# edges_v20.net
KiCad netlist of a schematic drawn in EAGLE
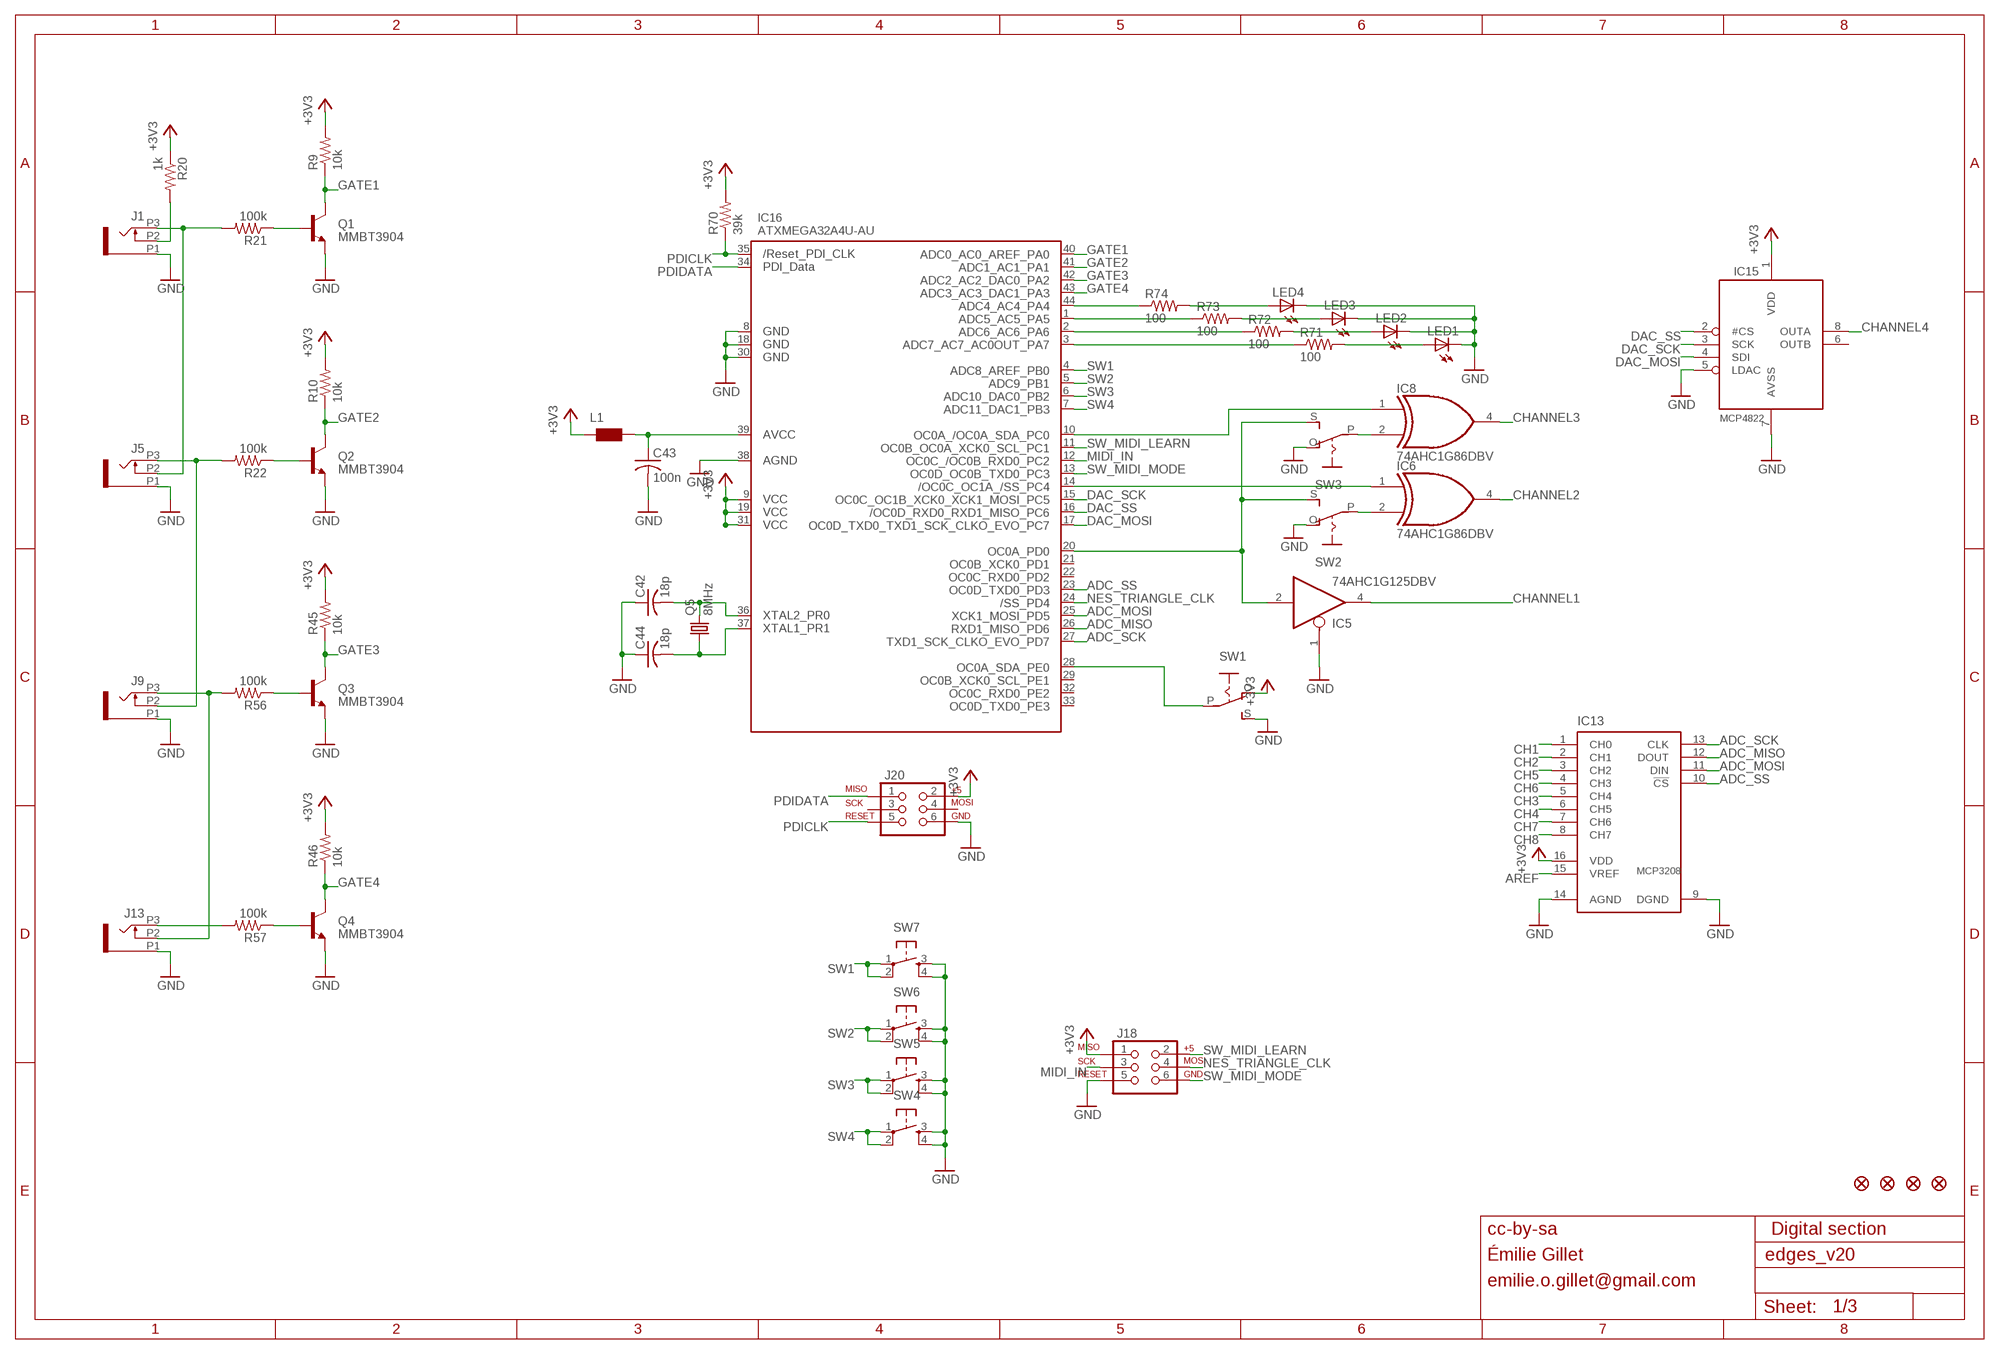
[diagram p0: schematic, sheet 1]
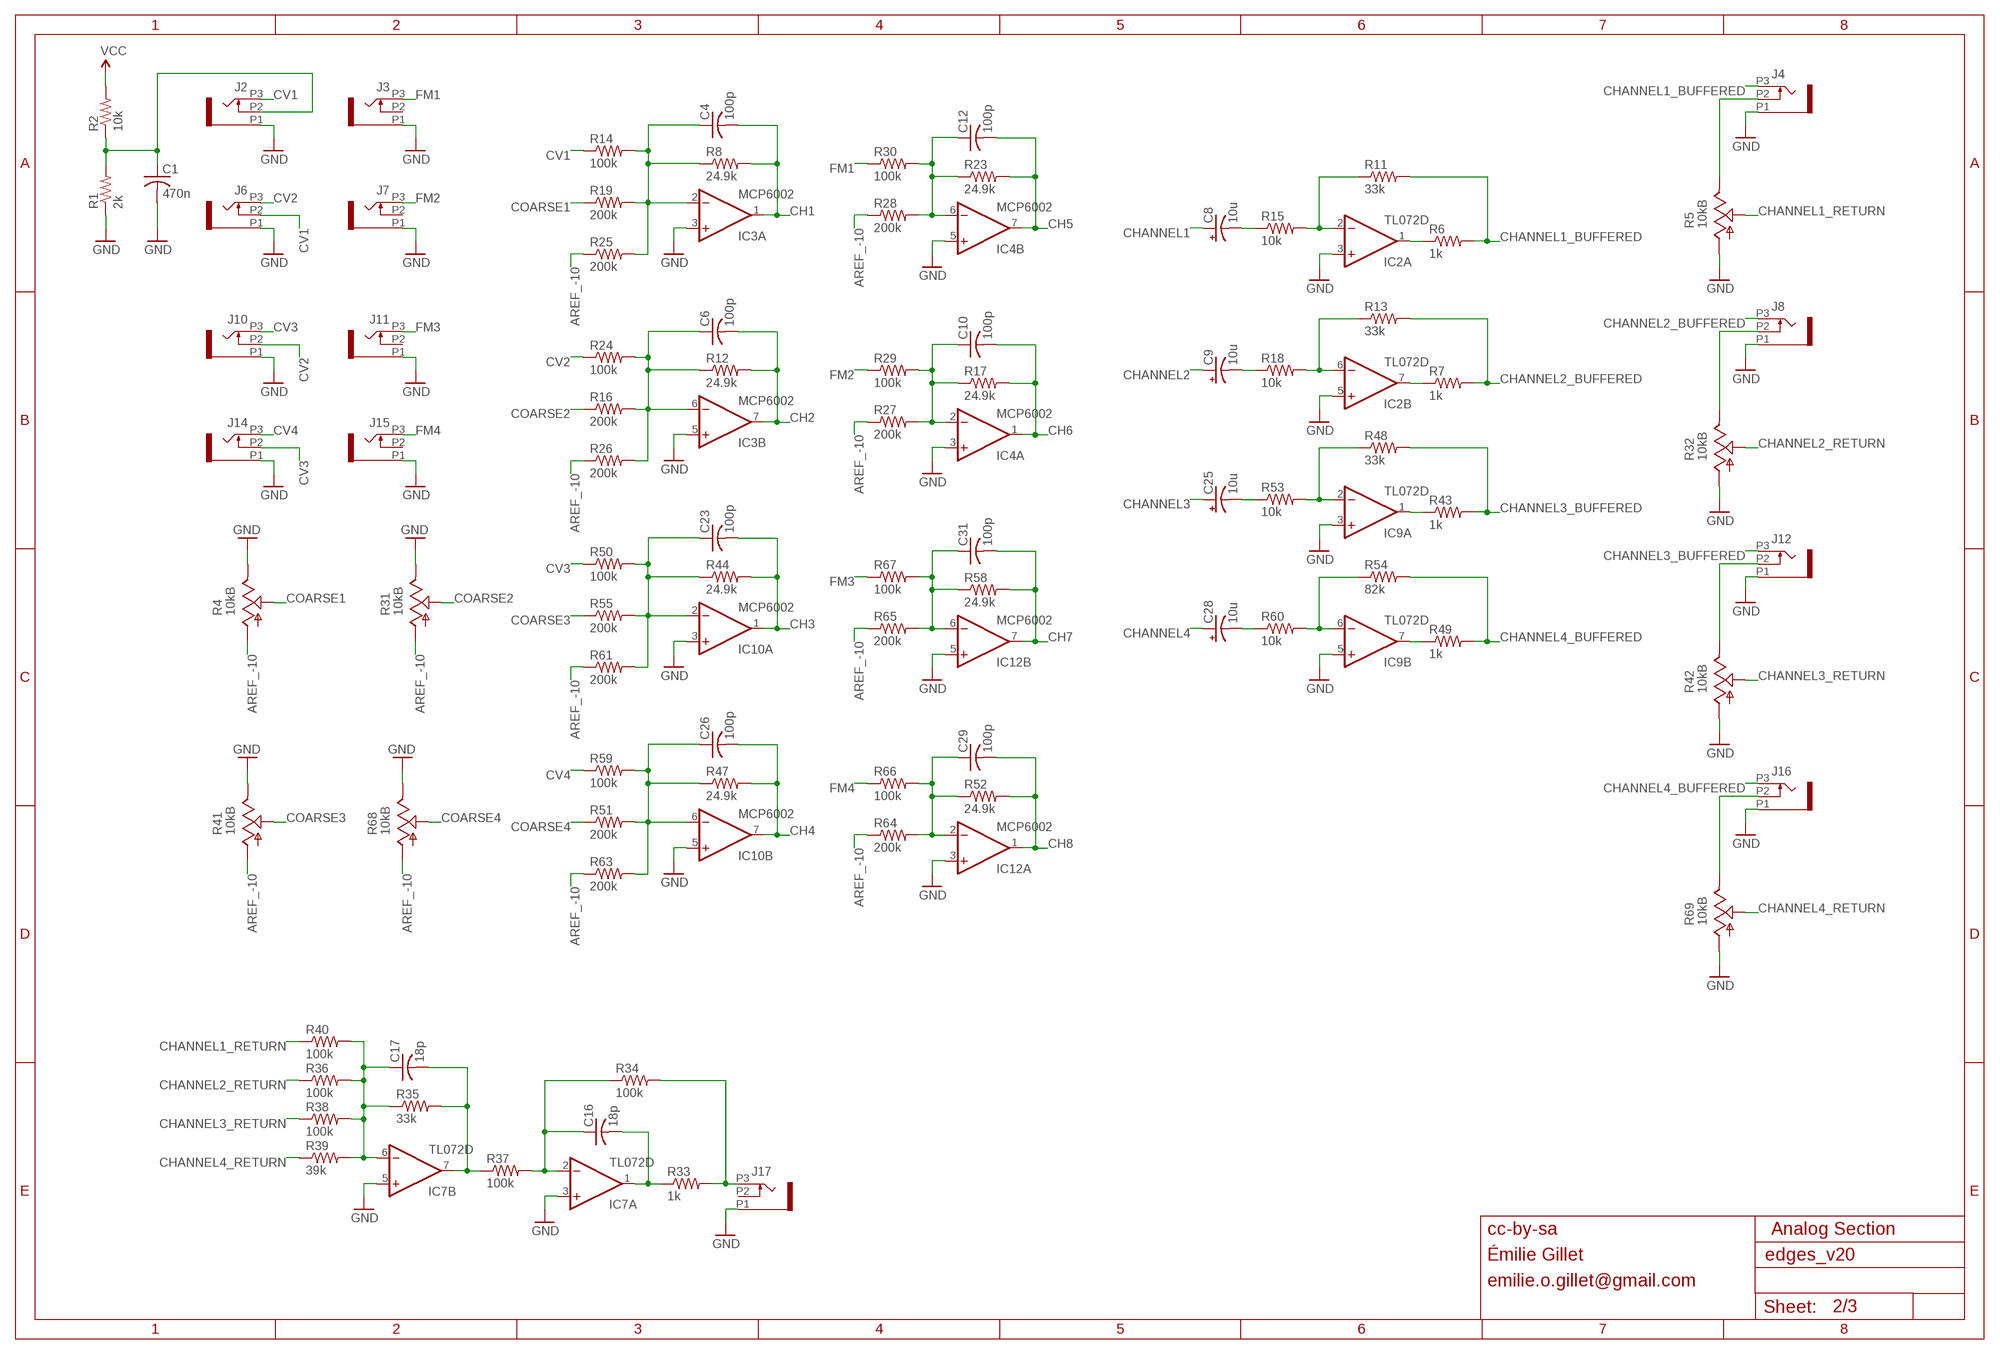
[diagram p1: schematic, sheet 2]
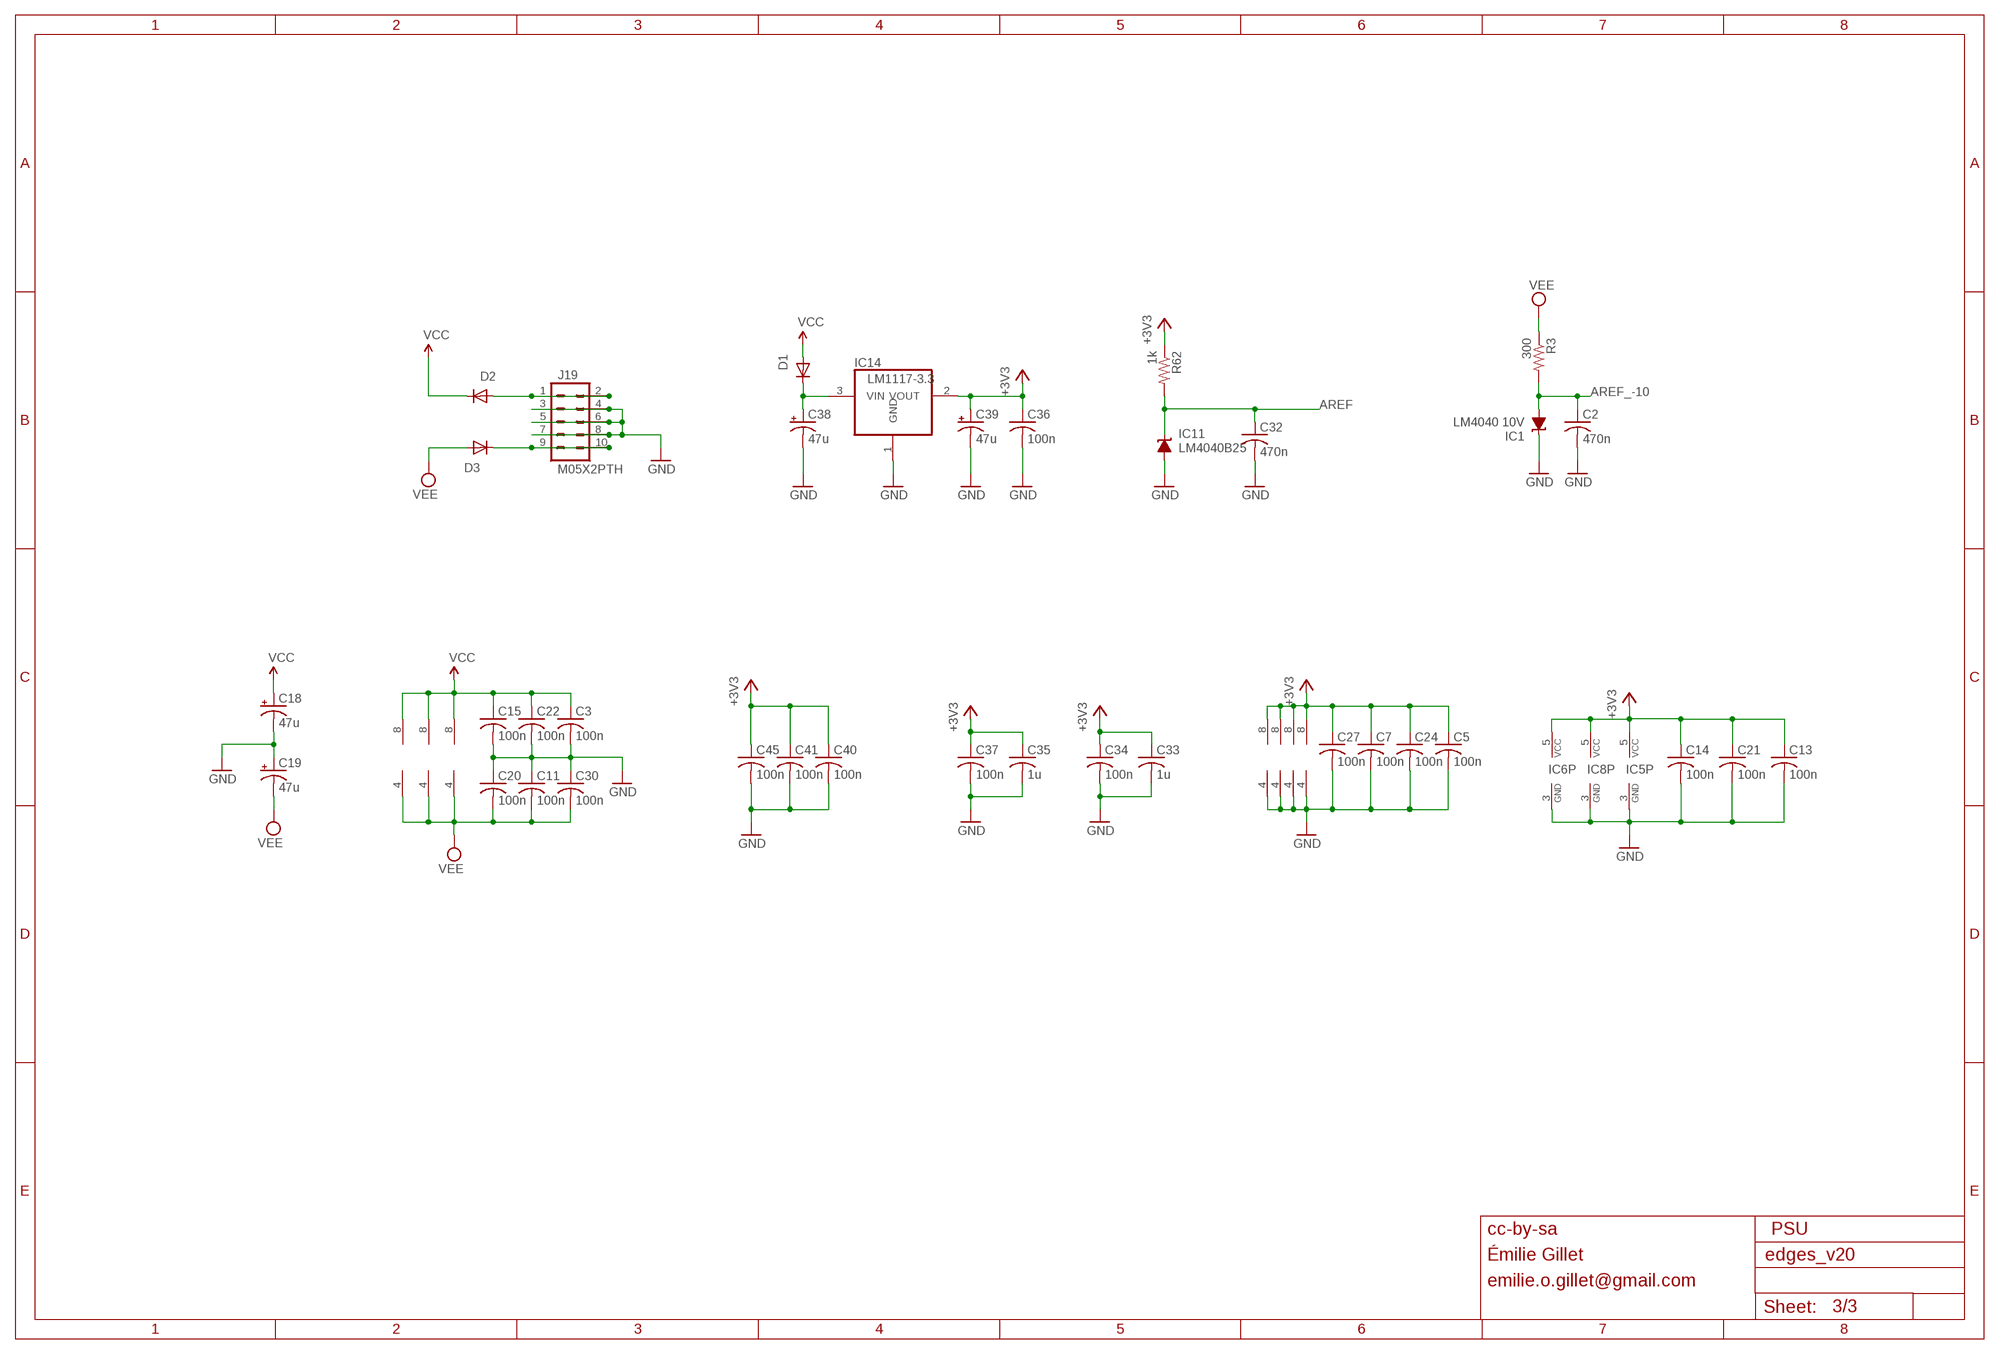
[diagram p2: schematic, sheet 3]

(export (version "E")
  (design (tool "Eeschema 10.0.6"))
  (components
    (comp (ref "C1")
      (value "470n")
      (footprint "eagle-import:C0603")
      (libsource (lib "eagle-import") (part "C-USC0603"))
    )
    (comp (ref "C4")
      (value "100p")
      (footprint "eagle-import:C0603")
      (libsource (lib "eagle-import") (part "C-USC0603"))
    )
    (comp (ref "C6")
      (value "100p")
      (footprint "eagle-import:C0603")
      (libsource (lib "eagle-import") (part "C-USC0603"))
    )
    (comp (ref "C8")
      (value "10u")
      (footprint "eagle-import:PANASONIC_B")
      (libsource (lib "eagle-import") (part "CPOL-USB"))
    )
    (comp (ref "C9")
      (value "10u")
      (footprint "eagle-import:PANASONIC_B")
      (libsource (lib "eagle-import") (part "CPOL-USB"))
    )
    (comp (ref "C10")
      (value "100p")
      (footprint "eagle-import:C0603")
      (libsource (lib "eagle-import") (part "C-USC0603"))
    )
    (comp (ref "C12")
      (value "100p")
      (footprint "eagle-import:C0603")
      (libsource (lib "eagle-import") (part "C-USC0603"))
    )
    (comp (ref "C16")
      (value "18p")
      (footprint "eagle-import:C0603")
      (libsource (lib "eagle-import") (part "C-USC0603"))
    )
    (comp (ref "C17")
      (value "18p")
      (footprint "eagle-import:C0603")
      (libsource (lib "eagle-import") (part "C-USC0603"))
    )
    (comp (ref "C23")
      (value "100p")
      (footprint "eagle-import:C0603")
      (libsource (lib "eagle-import") (part "C-USC0603"))
    )
    (comp (ref "C25")
      (value "10u")
      (footprint "eagle-import:PANASONIC_B")
      (libsource (lib "eagle-import") (part "CPOL-USB"))
    )
    (comp (ref "C26")
      (value "100p")
      (footprint "eagle-import:C0603")
      (libsource (lib "eagle-import") (part "C-USC0603"))
    )
    (comp (ref "C28")
      (value "10u")
      (footprint "eagle-import:PANASONIC_B")
      (libsource (lib "eagle-import") (part "CPOL-USB"))
    )
    (comp (ref "C29")
      (value "100p")
      (footprint "eagle-import:C0603")
      (libsource (lib "eagle-import") (part "C-USC0603"))
    )
    (comp (ref "C31")
      (value "100p")
      (footprint "eagle-import:C0603")
      (libsource (lib "eagle-import") (part "C-USC0603"))
    )
    (comp (ref "IC2")
      (value "TL072D")
      (footprint "eagle-import:SO08")
      (libsource (lib "eagle-import") (part "TL072D"))
    )
    (comp (ref "IC3")
      (value "MCP6002")
      (footprint "eagle-import:SO08")
      (libsource (lib "eagle-import") (part "TL072D"))
    )
    (comp (ref "IC4")
      (value "MCP6002")
      (footprint "eagle-import:SO08")
      (libsource (lib "eagle-import") (part "TL072D"))
    )
    (comp (ref "IC7")
      (value "TL072D")
      (footprint "eagle-import:SO08")
      (libsource (lib "eagle-import") (part "TL072D"))
    )
    (comp (ref "IC9")
      (value "TL072D")
      (footprint "eagle-import:SO08")
      (libsource (lib "eagle-import") (part "TL072D"))
    )
    (comp (ref "IC10")
      (value "MCP6002")
      (footprint "eagle-import:SO08")
      (libsource (lib "eagle-import") (part "TL072D"))
    )
    (comp (ref "IC12")
      (value "MCP6002")
      (footprint "eagle-import:SO08")
      (libsource (lib "eagle-import") (part "TL072D"))
    )
    (comp (ref "J2")
      (value "PJ301_THONKICONN6")
      (footprint "eagle-import:WQP_PJ_301M6")
      (libsource (lib "eagle-import") (part "PJ301_THONKICONN6"))
    )
    (comp (ref "J3")
      (value "PJ301_THONKICONN6")
      (footprint "eagle-import:WQP_PJ_301M6")
      (libsource (lib "eagle-import") (part "PJ301_THONKICONN6"))
    )
    (comp (ref "J4")
      (value "PJ301_THONKICONN6")
      (footprint "eagle-import:WQP_PJ_301M6")
      (libsource (lib "eagle-import") (part "PJ301_THONKICONN6"))
    )
    (comp (ref "J6")
      (value "PJ301_THONKICONN6")
      (footprint "eagle-import:WQP_PJ_301M6")
      (libsource (lib "eagle-import") (part "PJ301_THONKICONN6"))
    )
    (comp (ref "J7")
      (value "PJ301_THONKICONN6")
      (footprint "eagle-import:WQP_PJ_301M6")
      (libsource (lib "eagle-import") (part "PJ301_THONKICONN6"))
    )
    (comp (ref "J8")
      (value "PJ301_THONKICONN6")
      (footprint "eagle-import:WQP_PJ_301M6")
      (libsource (lib "eagle-import") (part "PJ301_THONKICONN6"))
    )
    (comp (ref "J10")
      (value "PJ301_THONKICONN6")
      (footprint "eagle-import:WQP_PJ_301M6")
      (libsource (lib "eagle-import") (part "PJ301_THONKICONN6"))
    )
    (comp (ref "J11")
      (value "PJ301_THONKICONN6")
      (footprint "eagle-import:WQP_PJ_301M6")
      (libsource (lib "eagle-import") (part "PJ301_THONKICONN6"))
    )
    (comp (ref "J12")
      (value "PJ301_THONKICONN6")
      (footprint "eagle-import:WQP_PJ_301M6")
      (libsource (lib "eagle-import") (part "PJ301_THONKICONN6"))
    )
    (comp (ref "J14")
      (value "PJ301_THONKICONN6")
      (footprint "eagle-import:WQP_PJ_301M6")
      (libsource (lib "eagle-import") (part "PJ301_THONKICONN6"))
    )
    (comp (ref "J15")
      (value "PJ301_THONKICONN6")
      (footprint "eagle-import:WQP_PJ_301M6")
      (libsource (lib "eagle-import") (part "PJ301_THONKICONN6"))
    )
    (comp (ref "J16")
      (value "PJ301_THONKICONN6")
      (footprint "eagle-import:WQP_PJ_301M6")
      (libsource (lib "eagle-import") (part "PJ301_THONKICONN6"))
    )
    (comp (ref "J17")
      (value "PJ301_THONKICONN6")
      (footprint "eagle-import:WQP_PJ_301M6")
      (libsource (lib "eagle-import") (part "PJ301_THONKICONN6"))
    )
    (comp (ref "R1")
      (value "2k")
      (footprint "eagle-import:R0603")
      (libsource (lib "eagle-import") (part "R-US_R0603"))
    )
    (comp (ref "R2")
      (value "10k")
      (footprint "eagle-import:R0603")
      (libsource (lib "eagle-import") (part "R-US_R0603"))
    )
    (comp (ref "R4")
      (value "10kB")
      (footprint "eagle-import:ALPS_POT_VERTICAL_PS")
      (libsource (lib "eagle-import") (part "POT_USVERTICAL_PS"))
    )
    (comp (ref "R5")
      (value "10kB")
      (footprint "eagle-import:ALPS_POT_VERTICAL_PS")
      (libsource (lib "eagle-import") (part "POT_USVERTICAL_PS"))
    )
    (comp (ref "R6")
      (value "1k")
      (footprint "eagle-import:R0603")
      (libsource (lib "eagle-import") (part "R-US_R0603"))
    )
    (comp (ref "R7")
      (value "1k")
      (footprint "eagle-import:R0603")
      (libsource (lib "eagle-import") (part "R-US_R0603"))
    )
    (comp (ref "R8")
      (value "24.9k")
      (footprint "eagle-import:R0603")
      (libsource (lib "eagle-import") (part "R-US_R0603"))
    )
    (comp (ref "R11")
      (value "33k")
      (footprint "eagle-import:R0603")
      (libsource (lib "eagle-import") (part "R-US_R0603"))
    )
    (comp (ref "R12")
      (value "24.9k")
      (footprint "eagle-import:R0603")
      (libsource (lib "eagle-import") (part "R-US_R0603"))
    )
    (comp (ref "R13")
      (value "33k")
      (footprint "eagle-import:R0603")
      (libsource (lib "eagle-import") (part "R-US_R0603"))
    )
    (comp (ref "R14")
      (value "100k")
      (footprint "eagle-import:R0603")
      (libsource (lib "eagle-import") (part "R-US_R0603"))
    )
    (comp (ref "R15")
      (value "10k")
      (footprint "eagle-import:R0603")
      (libsource (lib "eagle-import") (part "R-US_R0603"))
    )
    (comp (ref "R16")
      (value "200k")
      (footprint "eagle-import:R0603")
      (libsource (lib "eagle-import") (part "R-US_R0603"))
    )
    (comp (ref "R17")
      (value "24.9k")
      (footprint "eagle-import:R0603")
      (libsource (lib "eagle-import") (part "R-US_R0603"))
    )
    (comp (ref "R18")
      (value "10k")
      (footprint "eagle-import:R0603")
      (libsource (lib "eagle-import") (part "R-US_R0603"))
    )
    (comp (ref "R19")
      (value "200k")
      (footprint "eagle-import:R0603")
      (libsource (lib "eagle-import") (part "R-US_R0603"))
    )
    (comp (ref "R23")
      (value "24.9k")
      (footprint "eagle-import:R0603")
      (libsource (lib "eagle-import") (part "R-US_R0603"))
    )
    (comp (ref "R24")
      (value "100k")
      (footprint "eagle-import:R0603")
      (libsource (lib "eagle-import") (part "R-US_R0603"))
    )
    (comp (ref "R25")
      (value "200k")
      (footprint "eagle-import:R0603")
      (libsource (lib "eagle-import") (part "R-US_R0603"))
    )
    (comp (ref "R26")
      (value "200k")
      (footprint "eagle-import:R0603")
      (libsource (lib "eagle-import") (part "R-US_R0603"))
    )
    (comp (ref "R27")
      (value "200k")
      (footprint "eagle-import:R0603")
      (libsource (lib "eagle-import") (part "R-US_R0603"))
    )
    (comp (ref "R28")
      (value "200k")
      (footprint "eagle-import:R0603")
      (libsource (lib "eagle-import") (part "R-US_R0603"))
    )
    (comp (ref "R29")
      (value "100k")
      (footprint "eagle-import:R0603")
      (libsource (lib "eagle-import") (part "R-US_R0603"))
    )
    (comp (ref "R30")
      (value "100k")
      (footprint "eagle-import:R0603")
      (libsource (lib "eagle-import") (part "R-US_R0603"))
    )
    (comp (ref "R31")
      (value "10kB")
      (footprint "eagle-import:ALPS_POT_VERTICAL_PS")
      (libsource (lib "eagle-import") (part "POT_USVERTICAL_PS"))
    )
    (comp (ref "R32")
      (value "10kB")
      (footprint "eagle-import:ALPS_POT_VERTICAL_PS")
      (libsource (lib "eagle-import") (part "POT_USVERTICAL_PS"))
    )
    (comp (ref "R33")
      (value "1k")
      (footprint "eagle-import:R0603")
      (libsource (lib "eagle-import") (part "R-US_R0603"))
    )
    (comp (ref "R34")
      (value "100k")
      (footprint "eagle-import:R0603")
      (libsource (lib "eagle-import") (part "R-US_R0603"))
    )
    (comp (ref "R35")
      (value "33k")
      (footprint "eagle-import:R0603")
      (libsource (lib "eagle-import") (part "R-US_R0603"))
    )
    (comp (ref "R36")
      (value "100k")
      (footprint "eagle-import:R0603")
      (libsource (lib "eagle-import") (part "R-US_R0603"))
    )
    (comp (ref "R37")
      (value "100k")
      (footprint "eagle-import:R0603")
      (libsource (lib "eagle-import") (part "R-US_R0603"))
    )
    (comp (ref "R38")
      (value "100k")
      (footprint "eagle-import:R0603")
      (libsource (lib "eagle-import") (part "R-US_R0603"))
    )
    (comp (ref "R39")
      (value "39k")
      (footprint "eagle-import:R0603")
      (libsource (lib "eagle-import") (part "R-US_R0603"))
    )
    (comp (ref "R40")
      (value "100k")
      (footprint "eagle-import:R0603")
      (libsource (lib "eagle-import") (part "R-US_R0603"))
    )
    (comp (ref "R41")
      (value "10kB")
      (footprint "eagle-import:ALPS_POT_VERTICAL_PS")
      (libsource (lib "eagle-import") (part "POT_USVERTICAL_PS"))
    )
    (comp (ref "R42")
      (value "10kB")
      (footprint "eagle-import:ALPS_POT_VERTICAL_PS")
      (libsource (lib "eagle-import") (part "POT_USVERTICAL_PS"))
    )
    (comp (ref "R43")
      (value "1k")
      (footprint "eagle-import:R0603")
      (libsource (lib "eagle-import") (part "R-US_R0603"))
    )
    (comp (ref "R44")
      (value "24.9k")
      (footprint "eagle-import:R0603")
      (libsource (lib "eagle-import") (part "R-US_R0603"))
    )
    (comp (ref "R47")
      (value "24.9k")
      (footprint "eagle-import:R0603")
      (libsource (lib "eagle-import") (part "R-US_R0603"))
    )
    (comp (ref "R48")
      (value "33k")
      (footprint "eagle-import:R0603")
      (libsource (lib "eagle-import") (part "R-US_R0603"))
    )
    (comp (ref "R49")
      (value "1k")
      (footprint "eagle-import:R0603")
      (libsource (lib "eagle-import") (part "R-US_R0603"))
    )
    (comp (ref "R50")
      (value "100k")
      (footprint "eagle-import:R0603")
      (libsource (lib "eagle-import") (part "R-US_R0603"))
    )
    (comp (ref "R51")
      (value "200k")
      (footprint "eagle-import:R0603")
      (libsource (lib "eagle-import") (part "R-US_R0603"))
    )
    (comp (ref "R52")
      (value "24.9k")
      (footprint "eagle-import:R0603")
      (libsource (lib "eagle-import") (part "R-US_R0603"))
    )
    (comp (ref "R53")
      (value "10k")
      (footprint "eagle-import:R0603")
      (libsource (lib "eagle-import") (part "R-US_R0603"))
    )
    (comp (ref "R54")
      (value "82k")
      (footprint "eagle-import:R0603")
      (libsource (lib "eagle-import") (part "R-US_R0603"))
    )
    (comp (ref "R55")
      (value "200k")
      (footprint "eagle-import:R0603")
      (libsource (lib "eagle-import") (part "R-US_R0603"))
    )
    (comp (ref "R58")
      (value "24.9k")
      (footprint "eagle-import:R0603")
      (libsource (lib "eagle-import") (part "R-US_R0603"))
    )
    (comp (ref "R59")
      (value "100k")
      (footprint "eagle-import:R0603")
      (libsource (lib "eagle-import") (part "R-US_R0603"))
    )
    (comp (ref "R60")
      (value "10k")
      (footprint "eagle-import:R0603")
      (libsource (lib "eagle-import") (part "R-US_R0603"))
    )
    (comp (ref "R61")
      (value "200k")
      (footprint "eagle-import:R0603")
      (libsource (lib "eagle-import") (part "R-US_R0603"))
    )
    (comp (ref "R63")
      (value "200k")
      (footprint "eagle-import:R0603")
      (libsource (lib "eagle-import") (part "R-US_R0603"))
    )
    (comp (ref "R64")
      (value "200k")
      (footprint "eagle-import:R0603")
      (libsource (lib "eagle-import") (part "R-US_R0603"))
    )
    (comp (ref "R65")
      (value "200k")
      (footprint "eagle-import:R0603")
      (libsource (lib "eagle-import") (part "R-US_R0603"))
    )
    (comp (ref "R66")
      (value "100k")
      (footprint "eagle-import:R0603")
      (libsource (lib "eagle-import") (part "R-US_R0603"))
    )
    (comp (ref "R67")
      (value "100k")
      (footprint "eagle-import:R0603")
      (libsource (lib "eagle-import") (part "R-US_R0603"))
    )
    (comp (ref "R68")
      (value "10kB")
      (footprint "eagle-import:ALPS_POT_VERTICAL_PS")
      (libsource (lib "eagle-import") (part "POT_USVERTICAL_PS"))
    )
    (comp (ref "R69")
      (value "10kB")
      (footprint "eagle-import:ALPS_POT_VERTICAL_PS")
      (libsource (lib "eagle-import") (part "POT_USVERTICAL_PS"))
    )
    (comp (ref "C42")
      (value "18p")
      (footprint "eagle-import:C0603")
      (libsource (lib "eagle-import") (part "C-USC0603"))
    )
    (comp (ref "C43")
      (value "100n")
      (footprint "eagle-import:C0603")
      (libsource (lib "eagle-import") (part "C-USC0603"))
    )
    (comp (ref "C44")
      (value "18p")
      (footprint "eagle-import:C0603")
      (libsource (lib "eagle-import") (part "C-USC0603"))
    )
    (comp (ref "IC5")
      (value "74AHC1G125DBV")
      (footprint "eagle-import:SOT23-5")
      (libsource (lib "eagle-import") (part "741G125DBVAHC"))
    )
    (comp (ref "IC6")
      (value "74AHC1G86DBV")
      (footprint "eagle-import:SOT23-5")
      (libsource (lib "eagle-import") (part "741G86DBVAHC"))
    )
    (comp (ref "IC8")
      (value "74AHC1G86DBV")
      (footprint "eagle-import:SOT23-5")
      (libsource (lib "eagle-import") (part "741G86DBVAHC"))
    )
    (comp (ref "IC13")
      (value "MCP3208")
      (footprint "eagle-import:SO16")
      (libsource (lib "eagle-import") (part "MCP3208"))
    )
    (comp (ref "IC15")
      (value "MCP4822")
      (footprint "eagle-import:SO08")
      (libsource (lib "eagle-import") (part "MCP4822SO08"))
    )
    (comp (ref "IC16")
      (value "ATXMEGA32A4U-AU")
      (footprint "eagle-import:TQFP44")
      (libsource (lib "eagle-import") (part "AVR_XMEGA_A4_44A"))
    )
    (comp (ref "J1")
      (value "PJ301_THONKICONN6")
      (footprint "eagle-import:WQP_PJ_301M6")
      (libsource (lib "eagle-import") (part "PJ301_THONKICONN6"))
    )
    (comp (ref "J5")
      (value "PJ301_THONKICONN6")
      (footprint "eagle-import:WQP_PJ_301M6")
      (libsource (lib "eagle-import") (part "PJ301_THONKICONN6"))
    )
    (comp (ref "J9")
      (value "PJ301_THONKICONN6")
      (footprint "eagle-import:WQP_PJ_301M6")
      (libsource (lib "eagle-import") (part "PJ301_THONKICONN6"))
    )
    (comp (ref "J13")
      (value "PJ301_THONKICONN6")
      (footprint "eagle-import:WQP_PJ_301M6")
      (libsource (lib "eagle-import") (part "PJ301_THONKICONN6"))
    )
    (comp (ref "J18")
      (value "AVR_SPI_PRG_6PTH")
      (footprint "eagle-import:2X3")
      (libsource (lib "eagle-import") (part "AVR_SPI_PRG_6PTH"))
    )
    (comp (ref "J20")
      (value "AVR_SPI_PRG_6PTH")
      (footprint "eagle-import:2X3")
      (libsource (lib "eagle-import") (part "AVR_SPI_PRG_6PTH"))
    )
    (comp (ref "JP1")
      (value "FIDUCIAL1X2")
      (footprint "eagle-import:FIDUCIAL-1X2")
      (libsource (lib "eagle-import") (part "FIDUCIAL1X2"))
    )
    (comp (ref "JP2")
      (value "FIDUCIAL1X2")
      (footprint "eagle-import:FIDUCIAL-1X2")
      (libsource (lib "eagle-import") (part "FIDUCIAL1X2"))
    )
    (comp (ref "JP3")
      (value "FIDUCIAL1X2")
      (footprint "eagle-import:FIDUCIAL-1X2")
      (libsource (lib "eagle-import") (part "FIDUCIAL1X2"))
    )
    (comp (ref "JP4")
      (value "FIDUCIAL1X2")
      (footprint "eagle-import:FIDUCIAL-1X2")
      (libsource (lib "eagle-import") (part "FIDUCIAL1X2"))
    )
    (comp (ref "L1")
      (value "WE-CBF_0603")
      (footprint "eagle-import:0603")
      (libsource (lib "eagle-import") (part "WE-CBF_0603"))
    )
    (comp (ref "LED1")
      (value "LED3MM")
      (footprint "eagle-import:LED3MM")
      (libsource (lib "eagle-import") (part "LED3MM"))
    )
    (comp (ref "LED2")
      (value "LED3MM")
      (footprint "eagle-import:LED3MM")
      (libsource (lib "eagle-import") (part "LED3MM"))
    )
    (comp (ref "LED3")
      (value "LED3MM")
      (footprint "eagle-import:LED3MM")
      (libsource (lib "eagle-import") (part "LED3MM"))
    )
    (comp (ref "LED4")
      (value "LED3MM")
      (footprint "eagle-import:LED3MM")
      (libsource (lib "eagle-import") (part "LED3MM"))
    )
    (comp (ref "Q1")
      (value "MMBT3904")
      (footprint "eagle-import:SOT23-BEC")
      (libsource (lib "eagle-import") (part "-NPN-SOT23-BECMMBT3904LT1"))
    )
    (comp (ref "Q2")
      (value "MMBT3904")
      (footprint "eagle-import:SOT23-BEC")
      (libsource (lib "eagle-import") (part "-NPN-SOT23-BECMMBT3904LT1"))
    )
    (comp (ref "Q3")
      (value "MMBT3904")
      (footprint "eagle-import:SOT23-BEC")
      (libsource (lib "eagle-import") (part "-NPN-SOT23-BECMMBT3904LT1"))
    )
    (comp (ref "Q4")
      (value "MMBT3904")
      (footprint "eagle-import:SOT23-BEC")
      (libsource (lib "eagle-import") (part "-NPN-SOT23-BECMMBT3904LT1"))
    )
    (comp (ref "Q5")
      (value "8MHz")
      (footprint "eagle-import:HC49U70")
      (libsource (lib "eagle-import") (part "CRYSTALHC49U70"))
    )
    (comp (ref "R9")
      (value "10k")
      (footprint "eagle-import:R0603")
      (libsource (lib "eagle-import") (part "R-US_R0603"))
    )
    (comp (ref "R10")
      (value "10k")
      (footprint "eagle-import:R0603")
      (libsource (lib "eagle-import") (part "R-US_R0603"))
    )
    (comp (ref "R20")
      (value "1k")
      (footprint "eagle-import:R0603")
      (libsource (lib "eagle-import") (part "R-US_R0603"))
    )
    (comp (ref "R21")
      (value "100k")
      (footprint "eagle-import:R0603")
      (libsource (lib "eagle-import") (part "R-US_R0603"))
    )
    (comp (ref "R22")
      (value "100k")
      (footprint "eagle-import:R0603")
      (libsource (lib "eagle-import") (part "R-US_R0603"))
    )
    (comp (ref "R45")
      (value "10k")
      (footprint "eagle-import:R0603")
      (libsource (lib "eagle-import") (part "R-US_R0603"))
    )
    (comp (ref "R46")
      (value "10k")
      (footprint "eagle-import:R0603")
      (libsource (lib "eagle-import") (part "R-US_R0603"))
    )
    (comp (ref "R56")
      (value "100k")
      (footprint "eagle-import:R0603")
      (libsource (lib "eagle-import") (part "R-US_R0603"))
    )
    (comp (ref "R57")
      (value "100k")
      (footprint "eagle-import:R0603")
      (libsource (lib "eagle-import") (part "R-US_R0603"))
    )
    (comp (ref "R70")
      (value "39k")
      (footprint "eagle-import:R0603")
      (libsource (lib "eagle-import") (part "R-US_R0603"))
    )
    (comp (ref "R71")
      (value "100")
      (footprint "eagle-import:R0603")
      (libsource (lib "eagle-import") (part "R-US_R0603"))
    )
    (comp (ref "R72")
      (value "100")
      (footprint "eagle-import:R0603")
      (libsource (lib "eagle-import") (part "R-US_R0603"))
    )
    (comp (ref "R73")
      (value "100")
      (footprint "eagle-import:R0603")
      (libsource (lib "eagle-import") (part "R-US_R0603"))
    )
    (comp (ref "R74")
      (value "100")
      (footprint "eagle-import:R0603")
      (libsource (lib "eagle-import") (part "R-US_R0603"))
    )
    (comp (ref "SW1")
      (value "S-ON-ONSMALL_SLIDE")
      (footprint "eagle-import:ES_100SP1T6B11M2QEH_SMALL")
      (libsource (lib "eagle-import") (part "S-ON-ONSMALL_SLIDE"))
    )
    (comp (ref "SW2")
      (value "S-ON-ONSMALL_SLIDE")
      (footprint "eagle-import:ES_100SP1T6B11M2QEH_SMALL")
      (libsource (lib "eagle-import") (part "S-ON-ONSMALL_SLIDE"))
    )
    (comp (ref "SW3")
      (value "S-ON-ONSMALL_SLIDE")
      (footprint "eagle-import:ES_100SP1T6B11M2QEH_SMALL")
      (libsource (lib "eagle-import") (part "S-ON-ONSMALL_SLIDE"))
    )
    (comp (ref "SW4")
      (value "TAC_SWITCHPTH")
      (footprint "eagle-import:TACTILE-PTH")
      (libsource (lib "eagle-import") (part "TAC_SWITCHPTH"))
    )
    (comp (ref "SW5")
      (value "TAC_SWITCHPTH")
      (footprint "eagle-import:TACTILE-PTH")
      (libsource (lib "eagle-import") (part "TAC_SWITCHPTH"))
    )
    (comp (ref "SW6")
      (value "TAC_SWITCHPTH")
      (footprint "eagle-import:TACTILE-PTH")
      (libsource (lib "eagle-import") (part "TAC_SWITCHPTH"))
    )
    (comp (ref "SW7")
      (value "TAC_SWITCHPTH")
      (footprint "eagle-import:TACTILE-PTH")
      (libsource (lib "eagle-import") (part "TAC_SWITCHPTH"))
    )
    (comp (ref "C2")
      (value "470n")
      (footprint "eagle-import:C0603")
      (libsource (lib "eagle-import") (part "C-USC0603"))
    )
    (comp (ref "C3")
      (value "100n")
      (footprint "eagle-import:C0603")
      (libsource (lib "eagle-import") (part "C-USC0603"))
    )
    (comp (ref "C5")
      (value "100n")
      (footprint "eagle-import:C0603")
      (libsource (lib "eagle-import") (part "C-USC0603"))
    )
    (comp (ref "C7")
      (value "100n")
      (footprint "eagle-import:C0603")
      (libsource (lib "eagle-import") (part "C-USC0603"))
    )
    (comp (ref "C11")
      (value "100n")
      (footprint "eagle-import:C0603")
      (libsource (lib "eagle-import") (part "C-USC0603"))
    )
    (comp (ref "C13")
      (value "100n")
      (footprint "eagle-import:C0603")
      (libsource (lib "eagle-import") (part "C-USC0603"))
    )
    (comp (ref "C14")
      (value "100n")
      (footprint "eagle-import:C0603")
      (libsource (lib "eagle-import") (part "C-USC0603"))
    )
    (comp (ref "C15")
      (value "100n")
      (footprint "eagle-import:C0603")
      (libsource (lib "eagle-import") (part "C-USC0603"))
    )
    (comp (ref "C18")
      (value "47u")
      (footprint "eagle-import:PANASONIC_D")
      (libsource (lib "eagle-import") (part "CPOL-USD"))
    )
    (comp (ref "C19")
      (value "47u")
      (footprint "eagle-import:PANASONIC_D")
      (libsource (lib "eagle-import") (part "CPOL-USD"))
    )
    (comp (ref "C20")
      (value "100n")
      (footprint "eagle-import:C0603")
      (libsource (lib "eagle-import") (part "C-USC0603"))
    )
    (comp (ref "C21")
      (value "100n")
      (footprint "eagle-import:C0603")
      (libsource (lib "eagle-import") (part "C-USC0603"))
    )
    (comp (ref "C22")
      (value "100n")
      (footprint "eagle-import:C0603")
      (libsource (lib "eagle-import") (part "C-USC0603"))
    )
    (comp (ref "C24")
      (value "100n")
      (footprint "eagle-import:C0603")
      (libsource (lib "eagle-import") (part "C-USC0603"))
    )
    (comp (ref "C27")
      (value "100n")
      (footprint "eagle-import:C0603")
      (libsource (lib "eagle-import") (part "C-USC0603"))
    )
    (comp (ref "C30")
      (value "100n")
      (footprint "eagle-import:C0603")
      (libsource (lib "eagle-import") (part "C-USC0603"))
    )
    (comp (ref "C32")
      (value "470n")
      (footprint "eagle-import:C0603")
      (libsource (lib "eagle-import") (part "C-USC0603"))
    )
    (comp (ref "C33")
      (value "1u")
      (footprint "eagle-import:C0603")
      (libsource (lib "eagle-import") (part "C-USC0603"))
    )
    (comp (ref "C34")
      (value "100n")
      (footprint "eagle-import:C0603")
      (libsource (lib "eagle-import") (part "C-USC0603"))
    )
    (comp (ref "C35")
      (value "1u")
      (footprint "eagle-import:C0603")
      (libsource (lib "eagle-import") (part "C-USC0603"))
    )
    (comp (ref "C36")
      (value "100n")
      (footprint "eagle-import:C0603")
      (libsource (lib "eagle-import") (part "C-USC0603"))
    )
    (comp (ref "C37")
      (value "100n")
      (footprint "eagle-import:C0603")
      (libsource (lib "eagle-import") (part "C-USC0603"))
    )
    (comp (ref "C38")
      (value "47u")
      (footprint "eagle-import:PANASONIC_D")
      (libsource (lib "eagle-import") (part "CPOL-USD"))
    )
    (comp (ref "C39")
      (value "47u")
      (footprint "eagle-import:PANASONIC_D")
      (libsource (lib "eagle-import") (part "CPOL-USD"))
    )
    (comp (ref "C40")
      (value "100n")
      (footprint "eagle-import:C0603")
      (libsource (lib "eagle-import") (part "C-USC0603"))
    )
    (comp (ref "C41")
      (value "100n")
      (footprint "eagle-import:C0603")
      (libsource (lib "eagle-import") (part "C-USC0603"))
    )
    (comp (ref "C45")
      (value "100n")
      (footprint "eagle-import:C0603")
      (libsource (lib "eagle-import") (part "C-USC0603"))
    )
    (comp (ref "D1")
      (value "1N5819HW")
      (footprint "eagle-import:SOD123")
      (libsource (lib "eagle-import") (part "DIODE-SOD123"))
    )
    (comp (ref "D2")
      (value "1N5819HW")
      (footprint "eagle-import:SOD123")
      (libsource (lib "eagle-import") (part "DIODE-SOD123"))
    )
    (comp (ref "D3")
      (value "1N5819HW")
      (footprint "eagle-import:SOD123")
      (libsource (lib "eagle-import") (part "DIODE-SOD123"))
    )
    (comp (ref "IC1")
      (value "LM4040 10V")
      (footprint "eagle-import:DBZ_R-PDSO-G3")
      (libsource (lib "eagle-import") (part "LM4041DBZC12"))
    )
    (comp (ref "IC11")
      (value "LM4040B25")
      (footprint "eagle-import:DBZ_R-PDSO-G3")
      (libsource (lib "eagle-import") (part "LM4041DBZB12"))
    )
    (comp (ref "IC14")
      (value "LM1117-3.3")
      (footprint "eagle-import:SOT223")
      (libsource (lib "eagle-import") (part "REG1117"))
    )
    (comp (ref "J19")
      (value "M05X2PTH")
      (footprint "eagle-import:AVR_ICSP")
      (libsource (lib "eagle-import") (part "M05X2PTH"))
    )
    (comp (ref "R3")
      (value "300")
      (footprint "eagle-import:R0603")
      (libsource (lib "eagle-import") (part "resistor_R-US_R0603"))
    )
    (comp (ref "R62")
      (value "1k")
      (footprint "eagle-import:R0603")
      (libsource (lib "eagle-import") (part "R-US_R0603"))
    )
  )
  (nets
    (net (code "1") (name "+3V3") (class "Default")
      (node (ref "C13") (pin "1") (pinfunction "1_1") (pintype "passive"))
      (node (ref "C14") (pin "1") (pinfunction "1_1") (pintype "passive"))
      (node (ref "C21") (pin "1") (pinfunction "1_1") (pintype "passive"))
      (node (ref "C24") (pin "1") (pinfunction "1_1") (pintype "passive"))
      (node (ref "C27") (pin "1") (pinfunction "1_1") (pintype "passive"))
      (node (ref "C33") (pin "1") (pinfunction "1_1") (pintype "passive"))
      (node (ref "C34") (pin "1") (pinfunction "1_1") (pintype "passive"))
      (node (ref "C35") (pin "1") (pinfunction "1_1") (pintype "passive"))
      (node (ref "C36") (pin "1") (pinfunction "1_1") (pintype "passive"))
      (node (ref "C37") (pin "1") (pinfunction "1_1") (pintype "passive"))
      (node (ref "C39") (pin "+") (pinfunction "+_+") (pintype "passive"))
      (node (ref "C40") (pin "1") (pinfunction "1_1") (pintype "passive"))
      (node (ref "C41") (pin "1") (pinfunction "1_1") (pintype "passive"))
      (node (ref "C45") (pin "1") (pinfunction "1_1") (pintype "passive"))
      (node (ref "C5") (pin "1") (pinfunction "1_1") (pintype "passive"))
      (node (ref "C7") (pin "1") (pinfunction "1_1") (pintype "passive"))
      (node (ref "IC10") (pin "8") (pinfunction "V+_8") (pintype "power_in"))
      (node (ref "IC12") (pin "8") (pinfunction "V+_8") (pintype "power_in"))
      (node (ref "IC13") (pin "16") (pinfunction "VDD_16") (pintype "bidirectional"))
      (node (ref "IC14") (pin "2") (pinfunction "VOUT_2") (pintype "output"))
      (node (ref "IC15") (pin "1") (pinfunction "VDD_1") (pintype "power_in"))
      (node (ref "IC16") (pin "19") (pinfunction "VCC2_19") (pintype "bidirectional"))
      (node (ref "IC16") (pin "31") (pinfunction "VCC3_31") (pintype "bidirectional"))
      (node (ref "IC16") (pin "9") (pinfunction "VCC1_9") (pintype "bidirectional"))
      (node (ref "IC3") (pin "8") (pinfunction "V+_8") (pintype "power_in"))
      (node (ref "IC4") (pin "8") (pinfunction "V+_8") (pintype "power_in"))
      (node (ref "IC5") (pin "5") (pinfunction "VCC_5") (pintype "power_in"))
      (node (ref "IC6") (pin "5") (pinfunction "VCC_5") (pintype "power_in"))
      (node (ref "IC8") (pin "5") (pinfunction "VCC_5") (pintype "power_in"))
      (node (ref "J18") (pin "1") (pinfunction "1_1") (pintype "passive"))
      (node (ref "J20") (pin "2") (pinfunction "2_2") (pintype "passive"))
      (node (ref "L1") (pin "1") (pinfunction "1_1") (pintype "passive"))
      (node (ref "R10") (pin "2") (pinfunction "2_2") (pintype "passive"))
      (node (ref "R20") (pin "1") (pinfunction "1_1") (pintype "passive"))
      (node (ref "R45") (pin "2") (pinfunction "2_2") (pintype "passive"))
      (node (ref "R46") (pin "2") (pinfunction "2_2") (pintype "passive"))
      (node (ref "R62") (pin "1") (pinfunction "1_1") (pintype "passive"))
      (node (ref "R70") (pin "2") (pinfunction "2_2") (pintype "passive"))
      (node (ref "R9") (pin "2") (pinfunction "2_2") (pintype "passive"))
      (node (ref "SW1") (pin "O") (pinfunction "O_O") (pintype "passive"))
    )
    (net (code "2") (name "ADC_MISO") (class "Default")
      (node (ref "IC13") (pin "12") (pinfunction "DOUT_12") (pintype "bidirectional"))
      (node (ref "IC16") (pin "26") (pinfunction "PD6_26") (pintype "bidirectional"))
    )
    (net (code "3") (name "ADC_MOSI") (class "Default")
      (node (ref "IC13") (pin "11") (pinfunction "DIN_11") (pintype "bidirectional"))
      (node (ref "IC16") (pin "25") (pinfunction "PD5_25") (pintype "bidirectional"))
    )
    (net (code "4") (name "ADC_SCK") (class "Default")
      (node (ref "IC13") (pin "13") (pinfunction "CLK_13") (pintype "bidirectional"))
      (node (ref "IC16") (pin "27") (pinfunction "PD7_27") (pintype "bidirectional"))
    )
    (net (code "5") (name "ADC_SS") (class "Default")
      (node (ref "IC13") (pin "10") (pinfunction "~{CS}_10") (pintype "bidirectional"))
      (node (ref "IC16") (pin "23") (pinfunction "PD3_23") (pintype "bidirectional"))
    )
    (net (code "6") (name "AREF") (class "Default")
      (node (ref "C32") (pin "1") (pinfunction "1_1") (pintype "passive"))
      (node (ref "IC11") (pin "1") (pinfunction "C_1") (pintype "passive"))
      (node (ref "IC13") (pin "15") (pinfunction "VREF_15") (pintype "bidirectional"))
      (node (ref "R62") (pin "2") (pinfunction "2_2") (pintype "passive"))
    )
    (net (code "7") (name "AREF_-10") (class "Default")
      (node (ref "C2") (pin "1") (pinfunction "1_1") (pintype "passive"))
      (node (ref "IC1") (pin "2") (pinfunction "A_2") (pintype "passive"))
      (node (ref "R25") (pin "1") (pinfunction "1_1") (pintype "passive"))
      (node (ref "R26") (pin "1") (pinfunction "1_1") (pintype "passive"))
      (node (ref "R27") (pin "1") (pinfunction "1_1") (pintype "passive"))
      (node (ref "R28") (pin "1") (pinfunction "1_1") (pintype "passive"))
      (node (ref "R3") (pin "2") (pinfunction "2_2") (pintype "passive"))
      (node (ref "R31") (pin "P$3") (pinfunction "A_P$3") (pintype "passive"))
      (node (ref "R4") (pin "P$3") (pinfunction "A_P$3") (pintype "passive"))
      (node (ref "R41") (pin "P$3") (pinfunction "A_P$3") (pintype "passive"))
      (node (ref "R61") (pin "1") (pinfunction "1_1") (pintype "passive"))
      (node (ref "R63") (pin "1") (pinfunction "1_1") (pintype "passive"))
      (node (ref "R64") (pin "1") (pinfunction "1_1") (pintype "passive"))
      (node (ref "R65") (pin "1") (pinfunction "1_1") (pintype "passive"))
      (node (ref "R68") (pin "P$3") (pinfunction "A_P$3") (pintype "passive"))
    )
    (net (code "8") (name "CH1") (class "Default")
      (node (ref "C4") (pin "2") (pinfunction "2_2") (pintype "passive"))
      (node (ref "IC13") (pin "1") (pinfunction "CH0_1") (pintype "bidirectional"))
      (node (ref "IC3") (pin "1") (pinfunction "OUT_1") (pintype "output"))
      (node (ref "R8") (pin "2") (pinfunction "2_2") (pintype "passive"))
    )
    (net (code "9") (name "CH2") (class "Default")
      (node (ref "C6") (pin "2") (pinfunction "2_2") (pintype "passive"))
      (node (ref "IC13") (pin "2") (pinfunction "CH1_2") (pintype "bidirectional"))
      (node (ref "IC3") (pin "7") (pinfunction "OUT_7") (pintype "output"))
      (node (ref "R12") (pin "2") (pinfunction "2_2") (pintype "passive"))
    )
    (net (code "10") (name "CH3") (class "Default")
      (node (ref "C23") (pin "2") (pinfunction "2_2") (pintype "passive"))
      (node (ref "IC10") (pin "1") (pinfunction "OUT_1") (pintype "output"))
      (node (ref "IC13") (pin "5") (pinfunction "CH4_5") (pintype "bidirectional"))
      (node (ref "R44") (pin "2") (pinfunction "2_2") (pintype "passive"))
    )
    (net (code "11") (name "CH4") (class "Default")
      (node (ref "C26") (pin "2") (pinfunction "2_2") (pintype "passive"))
      (node (ref "IC10") (pin "7") (pinfunction "OUT_7") (pintype "output"))
      (node (ref "IC13") (pin "6") (pinfunction "CH5_6") (pintype "bidirectional"))
      (node (ref "R47") (pin "2") (pinfunction "2_2") (pintype "passive"))
    )
    (net (code "12") (name "CH5") (class "Default")
      (node (ref "C12") (pin "2") (pinfunction "2_2") (pintype "passive"))
      (node (ref "IC13") (pin "3") (pinfunction "CH2_3") (pintype "bidirectional"))
      (node (ref "IC4") (pin "7") (pinfunction "OUT_7") (pintype "output"))
      (node (ref "R23") (pin "2") (pinfunction "2_2") (pintype "passive"))
    )
    (net (code "13") (name "CH6") (class "Default")
      (node (ref "C10") (pin "2") (pinfunction "2_2") (pintype "passive"))
      (node (ref "IC13") (pin "4") (pinfunction "CH3_4") (pintype "bidirectional"))
      (node (ref "IC4") (pin "1") (pinfunction "OUT_1") (pintype "output"))
      (node (ref "R17") (pin "2") (pinfunction "2_2") (pintype "passive"))
    )
    (net (code "14") (name "CH7") (class "Default")
      (node (ref "C31") (pin "2") (pinfunction "2_2") (pintype "passive"))
      (node (ref "IC12") (pin "7") (pinfunction "OUT_7") (pintype "output"))
      (node (ref "IC13") (pin "7") (pinfunction "CH6_7") (pintype "bidirectional"))
      (node (ref "R58") (pin "2") (pinfunction "2_2") (pintype "passive"))
    )
    (net (code "15") (name "CH8") (class "Default")
      (node (ref "C29") (pin "2") (pinfunction "2_2") (pintype "passive"))
      (node (ref "IC12") (pin "1") (pinfunction "OUT_1") (pintype "output"))
      (node (ref "IC13") (pin "8") (pinfunction "CH7_8") (pintype "bidirectional"))
      (node (ref "R52") (pin "2") (pinfunction "2_2") (pintype "passive"))
    )
    (net (code "16") (name "CHANNEL1") (class "Default")
      (node (ref "C8") (pin "+") (pinfunction "+_+") (pintype "passive"))
      (node (ref "IC5") (pin "4") (pinfunction "O_4") (pintype "tri_state"))
    )
    (net (code "17") (name "CHANNEL1_BUFFERED") (class "Default")
      (node (ref "J4") (pin "P3") (pinfunction "3_P3") (pintype "passive"))
      (node (ref "R11") (pin "2") (pinfunction "2_2") (pintype "passive"))
      (node (ref "R6") (pin "2") (pinfunction "2_2") (pintype "passive"))
    )
    (net (code "18") (name "CHANNEL1_RETURN") (class "Default")
      (node (ref "R40") (pin "1") (pinfunction "1_1") (pintype "passive"))
      (node (ref "R5") (pin "P$2") (pinfunction "S_P$2") (pintype "passive"))
    )
    (net (code "19") (name "CHANNEL2") (class "Default")
      (node (ref "C9") (pin "+") (pinfunction "+_+") (pintype "passive"))
      (node (ref "IC6") (pin "4") (pinfunction "O_4") (pintype "output"))
    )
    (net (code "20") (name "CHANNEL2_BUFFERED") (class "Default")
      (node (ref "J8") (pin "P3") (pinfunction "3_P3") (pintype "passive"))
      (node (ref "R13") (pin "2") (pinfunction "2_2") (pintype "passive"))
      (node (ref "R7") (pin "2") (pinfunction "2_2") (pintype "passive"))
    )
    (net (code "21") (name "CHANNEL2_RETURN") (class "Default")
      (node (ref "R32") (pin "P$2") (pinfunction "S_P$2") (pintype "passive"))
      (node (ref "R36") (pin "1") (pinfunction "1_1") (pintype "passive"))
    )
    (net (code "22") (name "CHANNEL3") (class "Default")
      (node (ref "C25") (pin "+") (pinfunction "+_+") (pintype "passive"))
      (node (ref "IC8") (pin "4") (pinfunction "O_4") (pintype "output"))
    )
    (net (code "23") (name "CHANNEL3_BUFFERED") (class "Default")
      (node (ref "J12") (pin "P3") (pinfunction "3_P3") (pintype "passive"))
      (node (ref "R43") (pin "2") (pinfunction "2_2") (pintype "passive"))
      (node (ref "R48") (pin "2") (pinfunction "2_2") (pintype "passive"))
    )
    (net (code "24") (name "CHANNEL3_RETURN") (class "Default")
      (node (ref "R38") (pin "1") (pinfunction "1_1") (pintype "passive"))
      (node (ref "R42") (pin "P$2") (pinfunction "S_P$2") (pintype "passive"))
    )
    (net (code "25") (name "CHANNEL4") (class "Default")
      (node (ref "C28") (pin "+") (pinfunction "+_+") (pintype "passive"))
      (node (ref "IC15") (pin "8") (pinfunction "OUTA_8") (pintype "output"))
    )
    (net (code "26") (name "CHANNEL4_BUFFERED") (class "Default")
      (node (ref "J16") (pin "P3") (pinfunction "3_P3") (pintype "passive"))
      (node (ref "R49") (pin "2") (pinfunction "2_2") (pintype "passive"))
      (node (ref "R54") (pin "2") (pinfunction "2_2") (pintype "passive"))
    )
    (net (code "27") (name "CHANNEL4_RETURN") (class "Default")
      (node (ref "R39") (pin "1") (pinfunction "1_1") (pintype "passive"))
      (node (ref "R69") (pin "P$2") (pinfunction "S_P$2") (pintype "passive"))
    )
    (net (code "28") (name "COARSE1") (class "Default")
      (node (ref "R19") (pin "1") (pinfunction "1_1") (pintype "passive"))
      (node (ref "R4") (pin "P$2") (pinfunction "S_P$2") (pintype "passive"))
    )
    (net (code "29") (name "COARSE2") (class "Default")
      (node (ref "R16") (pin "1") (pinfunction "1_1") (pintype "passive"))
      (node (ref "R31") (pin "P$2") (pinfunction "S_P$2") (pintype "passive"))
    )
    (net (code "30") (name "COARSE3") (class "Default")
      (node (ref "R41") (pin "P$2") (pinfunction "S_P$2") (pintype "passive"))
      (node (ref "R55") (pin "1") (pinfunction "1_1") (pintype "passive"))
    )
    (net (code "31") (name "COARSE4") (class "Default")
      (node (ref "R51") (pin "1") (pinfunction "1_1") (pintype "passive"))
      (node (ref "R68") (pin "P$2") (pinfunction "S_P$2") (pintype "passive"))
    )
    (net (code "32") (name "CV1") (class "Default")
      (node (ref "J2") (pin "P3") (pinfunction "3_P3") (pintype "passive"))
      (node (ref "J6") (pin "P2") (pinfunction "2_P2") (pintype "passive"))
      (node (ref "R14") (pin "1") (pinfunction "1_1") (pintype "passive"))
    )
    (net (code "33") (name "CV2") (class "Default")
      (node (ref "J10") (pin "P2") (pinfunction "2_P2") (pintype "passive"))
      (node (ref "J6") (pin "P3") (pinfunction "3_P3") (pintype "passive"))
      (node (ref "R24") (pin "1") (pinfunction "1_1") (pintype "passive"))
    )
    (net (code "34") (name "CV3") (class "Default")
      (node (ref "J10") (pin "P3") (pinfunction "3_P3") (pintype "passive"))
      (node (ref "J14") (pin "P2") (pinfunction "2_P2") (pintype "passive"))
      (node (ref "R50") (pin "1") (pinfunction "1_1") (pintype "passive"))
    )
    (net (code "35") (name "CV4") (class "Default")
      (node (ref "J14") (pin "P3") (pinfunction "3_P3") (pintype "passive"))
      (node (ref "R59") (pin "1") (pinfunction "1_1") (pintype "passive"))
    )
    (net (code "36") (name "DAC_MOSI") (class "Default")
      (node (ref "IC15") (pin "4") (pinfunction "SDI_4") (pintype "input"))
      (node (ref "IC16") (pin "17") (pinfunction "PC7_17") (pintype "bidirectional"))
    )
    (net (code "37") (name "DAC_SCK") (class "Default")
      (node (ref "IC15") (pin "3") (pinfunction "SCK_3") (pintype "input"))
      (node (ref "IC16") (pin "15") (pinfunction "PC5_15") (pintype "bidirectional"))
    )
    (net (code "38") (name "DAC_SS") (class "Default")
      (node (ref "IC15") (pin "2") (pinfunction "#CS_2") (pintype "input"))
      (node (ref "IC16") (pin "16") (pinfunction "PC6_16") (pintype "bidirectional"))
    )
    (net (code "39") (name "FM1") (class "Default")
      (node (ref "J3") (pin "P3") (pinfunction "3_P3") (pintype "passive"))
      (node (ref "R30") (pin "1") (pinfunction "1_1") (pintype "passive"))
    )
    (net (code "40") (name "FM2") (class "Default")
      (node (ref "J7") (pin "P3") (pinfunction "3_P3") (pintype "passive"))
      (node (ref "R29") (pin "1") (pinfunction "1_1") (pintype "passive"))
    )
    (net (code "41") (name "FM3") (class "Default")
      (node (ref "J11") (pin "P3") (pinfunction "3_P3") (pintype "passive"))
      (node (ref "R67") (pin "1") (pinfunction "1_1") (pintype "passive"))
    )
    (net (code "42") (name "FM4") (class "Default")
      (node (ref "J15") (pin "P3") (pinfunction "3_P3") (pintype "passive"))
      (node (ref "R66") (pin "1") (pinfunction "1_1") (pintype "passive"))
    )
    (net (code "43") (name "GATE1") (class "Default")
      (node (ref "IC16") (pin "40") (pinfunction "PA0_40") (pintype "bidirectional"))
      (node (ref "Q1") (pin "C") (pinfunction "C_C") (pintype "passive"))
      (node (ref "R9") (pin "1") (pinfunction "1_1") (pintype "passive"))
    )
    (net (code "44") (name "GATE2") (class "Default")
      (node (ref "IC16") (pin "41") (pinfunction "PA1_41") (pintype "bidirectional"))
      (node (ref "Q2") (pin "C") (pinfunction "C_C") (pintype "passive"))
      (node (ref "R10") (pin "1") (pinfunction "1_1") (pintype "passive"))
    )
    (net (code "45") (name "GATE3") (class "Default")
      (node (ref "IC16") (pin "42") (pinfunction "PA2_42") (pintype "bidirectional"))
      (node (ref "Q3") (pin "C") (pinfunction "C_C") (pintype "passive"))
      (node (ref "R45") (pin "1") (pinfunction "1_1") (pintype "passive"))
    )
    (net (code "46") (name "GATE4") (class "Default")
      (node (ref "IC16") (pin "43") (pinfunction "PA3_43") (pintype "bidirectional"))
      (node (ref "Q4") (pin "C") (pinfunction "C_C") (pintype "passive"))
      (node (ref "R46") (pin "1") (pinfunction "1_1") (pintype "passive"))
    )
    (net (code "47") (name "GND") (class "Default")
      (node (ref "C1") (pin "2") (pinfunction "2_2") (pintype "passive"))
      (node (ref "C11") (pin "1") (pinfunction "1_1") (pintype "passive"))
      (node (ref "C13") (pin "2") (pinfunction "2_2") (pintype "passive"))
      (node (ref "C14") (pin "2") (pinfunction "2_2") (pintype "passive"))
      (node (ref "C15") (pin "2") (pinfunction "2_2") (pintype "passive"))
      (node (ref "C18") (pin "-") (pinfunction "-_-") (pintype "passive"))
      (node (ref "C19") (pin "+") (pinfunction "+_+") (pintype "passive"))
      (node (ref "C2") (pin "2") (pinfunction "2_2") (pintype "passive"))
      (node (ref "C20") (pin "1") (pinfunction "1_1") (pintype "passive"))
      (node (ref "C21") (pin "2") (pinfunction "2_2") (pintype "passive"))
      (node (ref "C22") (pin "2") (pinfunction "2_2") (pintype "passive"))
      (node (ref "C24") (pin "2") (pinfunction "2_2") (pintype "passive"))
      (node (ref "C27") (pin "2") (pinfunction "2_2") (pintype "passive"))
      (node (ref "C3") (pin "2") (pinfunction "2_2") (pintype "passive"))
      (node (ref "C30") (pin "1") (pinfunction "1_1") (pintype "passive"))
      (node (ref "C32") (pin "2") (pinfunction "2_2") (pintype "passive"))
      (node (ref "C33") (pin "2") (pinfunction "2_2") (pintype "passive"))
      (node (ref "C34") (pin "2") (pinfunction "2_2") (pintype "passive"))
      (node (ref "C35") (pin "2") (pinfunction "2_2") (pintype "passive"))
      (node (ref "C36") (pin "2") (pinfunction "2_2") (pintype "passive"))
      (node (ref "C37") (pin "2") (pinfunction "2_2") (pintype "passive"))
      (node (ref "C38") (pin "-") (pinfunction "-_-") (pintype "passive"))
      (node (ref "C39") (pin "-") (pinfunction "-_-") (pintype "passive"))
      (node (ref "C40") (pin "2") (pinfunction "2_2") (pintype "passive"))
      (node (ref "C41") (pin "2") (pinfunction "2_2") (pintype "passive"))
      (node (ref "C42") (pin "1") (pinfunction "1_1") (pintype "passive"))
      (node (ref "C43") (pin "2") (pinfunction "2_2") (pintype "passive"))
      (node (ref "C44") (pin "1") (pinfunction "1_1") (pintype "passive"))
      (node (ref "C45") (pin "2") (pinfunction "2_2") (pintype "passive"))
      (node (ref "C5") (pin "2") (pinfunction "2_2") (pintype "passive"))
      (node (ref "C7") (pin "2") (pinfunction "2_2") (pintype "passive"))
      (node (ref "IC1") (pin "1") (pinfunction "C_1") (pintype "passive"))
      (node (ref "IC10") (pin "3") (pinfunction "+IN_3") (pintype "input"))
      (node (ref "IC10") (pin "4") (pinfunction "V-_4") (pintype "power_in"))
      (node (ref "IC10") (pin "5") (pinfunction "+IN_5") (pintype "input"))
      (node (ref "IC11") (pin "2") (pinfunction "A_2") (pintype "passive"))
      (node (ref "IC12") (pin "3") (pinfunction "+IN_3") (pintype "input"))
      (node (ref "IC12") (pin "4") (pinfunction "V-_4") (pintype "power_in"))
      (node (ref "IC12") (pin "5") (pinfunction "+IN_5") (pintype "input"))
      (node (ref "IC13") (pin "14") (pinfunction "AGND_14") (pintype "bidirectional"))
      (node (ref "IC13") (pin "9") (pinfunction "DGND_9") (pintype "bidirectional"))
      (node (ref "IC14") (pin "1") (pinfunction "GND_1") (pintype "power_in"))
      (node (ref "IC15") (pin "5") (pinfunction "LDAC_5") (pintype "input"))
      (node (ref "IC15") (pin "7") (pinfunction "AVSS_7") (pintype "power_in"))
      (node (ref "IC16") (pin "18") (pinfunction "GND2_18") (pintype "bidirectional"))
      (node (ref "IC16") (pin "30") (pinfunction "GND3_30") (pintype "bidirectional"))
      (node (ref "IC16") (pin "38") (pinfunction "AGND_38") (pintype "bidirectional"))
      (node (ref "IC16") (pin "8") (pinfunction "GND1_8") (pintype "bidirectional"))
      (node (ref "IC2") (pin "3") (pinfunction "+IN_3") (pintype "input"))
      (node (ref "IC2") (pin "5") (pinfunction "+IN_5") (pintype "input"))
      (node (ref "IC3") (pin "3") (pinfunction "+IN_3") (pintype "input"))
      (node (ref "IC3") (pin "4") (pinfunction "V-_4") (pintype "power_in"))
      (node (ref "IC3") (pin "5") (pinfunction "+IN_5") (pintype "input"))
      (node (ref "IC4") (pin "3") (pinfunction "+IN_3") (pintype "input"))
      (node (ref "IC4") (pin "4") (pinfunction "V-_4") (pintype "power_in"))
      (node (ref "IC4") (pin "5") (pinfunction "+IN_5") (pintype "input"))
      (node (ref "IC5") (pin "1") (pinfunction "OE_1") (pintype "input"))
      (node (ref "IC5") (pin "3") (pinfunction "GND_3") (pintype "power_in"))
      (node (ref "IC6") (pin "3") (pinfunction "GND_3") (pintype "power_in"))
      (node (ref "IC7") (pin "3") (pinfunction "+IN_3") (pintype "input"))
      (node (ref "IC7") (pin "5") (pinfunction "+IN_5") (pintype "input"))
      (node (ref "IC8") (pin "3") (pinfunction "GND_3") (pintype "power_in"))
      (node (ref "IC9") (pin "3") (pinfunction "+IN_3") (pintype "input"))
      (node (ref "IC9") (pin "5") (pinfunction "+IN_5") (pintype "input"))
      (node (ref "J1") (pin "P1") (pinfunction "1_P1") (pintype "passive"))
      (node (ref "J10") (pin "P1") (pinfunction "1_P1") (pintype "passive"))
      (node (ref "J11") (pin "P1") (pinfunction "1_P1") (pintype "passive"))
      (node (ref "J12") (pin "P1") (pinfunction "1_P1") (pintype "passive"))
      (node (ref "J13") (pin "P1") (pinfunction "1_P1") (pintype "passive"))
      (node (ref "J14") (pin "P1") (pinfunction "1_P1") (pintype "passive"))
      (node (ref "J15") (pin "P1") (pinfunction "1_P1") (pintype "passive"))
      (node (ref "J16") (pin "P1") (pinfunction "1_P1") (pintype "passive"))
      (node (ref "J17") (pin "P1") (pinfunction "1_P1") (pintype "passive"))
      (node (ref "J18") (pin "5") (pinfunction "5_5") (pintype "passive"))
      (node (ref "J19") (pin "3") (pinfunction "3_3") (pintype "passive"))
      (node (ref "J19") (pin "4") (pinfunction "4_4") (pintype "passive"))
      (node (ref "J19") (pin "5") (pinfunction "5_5") (pintype "passive"))
      (node (ref "J19") (pin "6") (pinfunction "6_6") (pintype "passive"))
      (node (ref "J19") (pin "7") (pinfunction "7_7") (pintype "passive"))
      (node (ref "J19") (pin "8") (pinfunction "8_8") (pintype "passive"))
      (node (ref "J2") (pin "P1") (pinfunction "1_P1") (pintype "passive"))
      (node (ref "J20") (pin "6") (pinfunction "6_6") (pintype "passive"))
      (node (ref "J3") (pin "P1") (pinfunction "1_P1") (pintype "passive"))
      (node (ref "J4") (pin "P1") (pinfunction "1_P1") (pintype "passive"))
      (node (ref "J5") (pin "P1") (pinfunction "1_P1") (pintype "passive"))
      (node (ref "J6") (pin "P1") (pinfunction "1_P1") (pintype "passive"))
      (node (ref "J7") (pin "P1") (pinfunction "1_P1") (pintype "passive"))
      (node (ref "J8") (pin "P1") (pinfunction "1_P1") (pintype "passive"))
      (node (ref "J9") (pin "P1") (pinfunction "1_P1") (pintype "passive"))
      (node (ref "LED1") (pin "K") (pinfunction "C_K") (pintype "passive"))
      (node (ref "LED2") (pin "K") (pinfunction "C_K") (pintype "passive"))
      (node (ref "LED3") (pin "K") (pinfunction "C_K") (pintype "passive"))
      (node (ref "LED4") (pin "K") (pinfunction "C_K") (pintype "passive"))
      (node (ref "Q1") (pin "E") (pinfunction "E_E") (pintype "passive"))
      (node (ref "Q2") (pin "E") (pinfunction "E_E") (pintype "passive"))
      (node (ref "Q3") (pin "E") (pinfunction "E_E") (pintype "passive"))
      (node (ref "Q4") (pin "E") (pinfunction "E_E") (pintype "passive"))
      (node (ref "R1") (pin "1") (pinfunction "1_1") (pintype "passive"))
      (node (ref "R31") (pin "P$1") (pinfunction "E_P$1") (pintype "passive"))
      (node (ref "R32") (pin "P$3") (pinfunction "A_P$3") (pintype "passive"))
      (node (ref "R4") (pin "P$1") (pinfunction "E_P$1") (pintype "passive"))
      (node (ref "R41") (pin "P$1") (pinfunction "E_P$1") (pintype "passive"))
      (node (ref "R42") (pin "P$3") (pinfunction "A_P$3") (pintype "passive"))
      (node (ref "R5") (pin "P$3") (pinfunction "A_P$3") (pintype "passive"))
      (node (ref "R68") (pin "P$1") (pinfunction "E_P$1") (pintype "passive"))
      (node (ref "R69") (pin "P$3") (pinfunction "A_P$3") (pintype "passive"))
      (node (ref "SW1") (pin "S") (pinfunction "S_S") (pintype "passive"))
      (node (ref "SW2") (pin "O") (pinfunction "O_O") (pintype "passive"))
      (node (ref "SW3") (pin "O") (pinfunction "O_O") (pintype "passive"))
      (node (ref "SW4") (pin "3") (pinfunction "3_3") (pintype "passive"))
      (node (ref "SW4") (pin "4") (pinfunction "4_4") (pintype "passive"))
      (node (ref "SW5") (pin "3") (pinfunction "3_3") (pintype "passive"))
      (node (ref "SW5") (pin "4") (pinfunction "4_4") (pintype "passive"))
      (node (ref "SW6") (pin "3") (pinfunction "3_3") (pintype "passive"))
      (node (ref "SW6") (pin "4") (pinfunction "4_4") (pintype "passive"))
      (node (ref "SW7") (pin "3") (pinfunction "3_3") (pintype "passive"))
      (node (ref "SW7") (pin "4") (pinfunction "4_4") (pintype "passive"))
    )
    (net (code "48") (name "MIDI_IN") (class "Default")
      (node (ref "IC16") (pin "12") (pinfunction "PC2_12") (pintype "bidirectional"))
      (node (ref "J18") (pin "3") (pinfunction "3_3") (pintype "passive"))
    )
    (net (code "49") (name "NES_TRIANGLE_CLK") (class "Default")
      (node (ref "IC16") (pin "24") (pinfunction "PD4_24") (pintype "bidirectional"))
      (node (ref "J18") (pin "4") (pinfunction "4_4") (pintype "passive"))
    )
    (net (code "50") (name "Net-(C8-Pad-)") (class "Default")
      (node (ref "C8") (pin "-") (pinfunction "-_-") (pintype "passive"))
      (node (ref "R15") (pin "1") (pinfunction "1_1") (pintype "passive"))
    )
    (net (code "51") (name "Net-(C9-Pad-)") (class "Default")
      (node (ref "C9") (pin "-") (pinfunction "-_-") (pintype "passive"))
      (node (ref "R18") (pin "1") (pinfunction "1_1") (pintype "passive"))
    )
    (net (code "52") (name "Net-(C25-Pad-)") (class "Default")
      (node (ref "C25") (pin "-") (pinfunction "-_-") (pintype "passive"))
      (node (ref "R53") (pin "1") (pinfunction "1_1") (pintype "passive"))
    )
    (net (code "53") (name "Net-(C28-Pad-)") (class "Default")
      (node (ref "C28") (pin "-") (pinfunction "-_-") (pintype "passive"))
      (node (ref "R60") (pin "1") (pinfunction "1_1") (pintype "passive"))
    )
    (net (code "54") (name "Net-(D2-PadA)") (class "Default")
      (node (ref "D2") (pin "A") (pinfunction "A_A") (pintype "passive"))
      (node (ref "J19") (pin "1") (pinfunction "1_1") (pintype "passive"))
      (node (ref "J19") (pin "2") (pinfunction "2_2") (pintype "passive"))
    )
    (net (code "55") (name "Net-(D3-PadC)") (class "Default")
      (node (ref "D3") (pin "C") (pinfunction "C_C") (pintype "passive"))
      (node (ref "J19") (pin "10") (pinfunction "10_10") (pintype "passive"))
      (node (ref "J19") (pin "9") (pinfunction "9_9") (pintype "passive"))
    )
    (net (code "56") (name "Net-(IC2A--IN)") (class "Default")
      (node (ref "IC2") (pin "2") (pinfunction "-IN_2") (pintype "input"))
      (node (ref "R11") (pin "1") (pinfunction "1_1") (pintype "passive"))
      (node (ref "R15") (pin "2") (pinfunction "2_2") (pintype "passive"))
    )
    (net (code "57") (name "Net-(IC2A-OUT)") (class "Default")
      (node (ref "IC2") (pin "1") (pinfunction "OUT_1") (pintype "output"))
      (node (ref "R6") (pin "1") (pinfunction "1_1") (pintype "passive"))
    )
    (net (code "58") (name "Net-(IC2B--IN)") (class "Default")
      (node (ref "IC2") (pin "6") (pinfunction "-IN_6") (pintype "input"))
      (node (ref "R13") (pin "1") (pinfunction "1_1") (pintype "passive"))
      (node (ref "R18") (pin "2") (pinfunction "2_2") (pintype "passive"))
    )
    (net (code "59") (name "Net-(IC2B-OUT)") (class "Default")
      (node (ref "IC2") (pin "7") (pinfunction "OUT_7") (pintype "output"))
      (node (ref "R7") (pin "1") (pinfunction "1_1") (pintype "passive"))
    )
    (net (code "60") (name "Net-(IC3A--IN)") (class "Default")
      (node (ref "C4") (pin "1") (pinfunction "1_1") (pintype "passive"))
      (node (ref "IC3") (pin "2") (pinfunction "-IN_2") (pintype "input"))
      (node (ref "R14") (pin "2") (pinfunction "2_2") (pintype "passive"))
      (node (ref "R19") (pin "2") (pinfunction "2_2") (pintype "passive"))
      (node (ref "R25") (pin "2") (pinfunction "2_2") (pintype "passive"))
      (node (ref "R8") (pin "1") (pinfunction "1_1") (pintype "passive"))
    )
    (net (code "61") (name "Net-(IC3B--IN)") (class "Default")
      (node (ref "C6") (pin "1") (pinfunction "1_1") (pintype "passive"))
      (node (ref "IC3") (pin "6") (pinfunction "-IN_6") (pintype "input"))
      (node (ref "R12") (pin "1") (pinfunction "1_1") (pintype "passive"))
      (node (ref "R16") (pin "2") (pinfunction "2_2") (pintype "passive"))
      (node (ref "R24") (pin "2") (pinfunction "2_2") (pintype "passive"))
      (node (ref "R26") (pin "2") (pinfunction "2_2") (pintype "passive"))
    )
    (net (code "62") (name "Net-(IC4A--IN)") (class "Default")
      (node (ref "C10") (pin "1") (pinfunction "1_1") (pintype "passive"))
      (node (ref "IC4") (pin "2") (pinfunction "-IN_2") (pintype "input"))
      (node (ref "R17") (pin "1") (pinfunction "1_1") (pintype "passive"))
      (node (ref "R27") (pin "2") (pinfunction "2_2") (pintype "passive"))
      (node (ref "R29") (pin "2") (pinfunction "2_2") (pintype "passive"))
    )
    (net (code "63") (name "Net-(IC4B--IN)") (class "Default")
      (node (ref "C12") (pin "1") (pinfunction "1_1") (pintype "passive"))
      (node (ref "IC4") (pin "6") (pinfunction "-IN_6") (pintype "input"))
      (node (ref "R23") (pin "1") (pinfunction "1_1") (pintype "passive"))
      (node (ref "R28") (pin "2") (pinfunction "2_2") (pintype "passive"))
      (node (ref "R30") (pin "2") (pinfunction "2_2") (pintype "passive"))
    )
    (net (code "64") (name "Net-(IC6A-I1)") (class "Default")
      (node (ref "IC6") (pin "2") (pinfunction "I1_2") (pintype "input"))
      (node (ref "SW2") (pin "P") (pinfunction "P_P") (pintype "passive"))
    )
    (net (code "65") (name "Net-(IC7A--IN)") (class "Default")
      (node (ref "C16") (pin "1") (pinfunction "1_1") (pintype "passive"))
      (node (ref "IC7") (pin "2") (pinfunction "-IN_2") (pintype "input"))
      (node (ref "R34") (pin "1") (pinfunction "1_1") (pintype "passive"))
      (node (ref "R37") (pin "2") (pinfunction "2_2") (pintype "passive"))
    )
    (net (code "66") (name "Net-(IC7A-OUT)") (class "Default")
      (node (ref "C16") (pin "2") (pinfunction "2_2") (pintype "passive"))
      (node (ref "IC7") (pin "1") (pinfunction "OUT_1") (pintype "output"))
      (node (ref "R33") (pin "1") (pinfunction "1_1") (pintype "passive"))
    )
    (net (code "67") (name "Net-(IC7B--IN)") (class "Default")
      (node (ref "C17") (pin "1") (pinfunction "1_1") (pintype "passive"))
      (node (ref "IC7") (pin "6") (pinfunction "-IN_6") (pintype "input"))
      (node (ref "R35") (pin "1") (pinfunction "1_1") (pintype "passive"))
      (node (ref "R36") (pin "2") (pinfunction "2_2") (pintype "passive"))
      (node (ref "R38") (pin "2") (pinfunction "2_2") (pintype "passive"))
      (node (ref "R39") (pin "2") (pinfunction "2_2") (pintype "passive"))
      (node (ref "R40") (pin "2") (pinfunction "2_2") (pintype "passive"))
    )
    (net (code "68") (name "Net-(IC7B-OUT)") (class "Default")
      (node (ref "C17") (pin "2") (pinfunction "2_2") (pintype "passive"))
      (node (ref "IC7") (pin "7") (pinfunction "OUT_7") (pintype "output"))
      (node (ref "R35") (pin "2") (pinfunction "2_2") (pintype "passive"))
      (node (ref "R37") (pin "1") (pinfunction "1_1") (pintype "passive"))
    )
    (net (code "69") (name "Net-(IC8A-I1)") (class "Default")
      (node (ref "IC8") (pin "2") (pinfunction "I1_2") (pintype "input"))
      (node (ref "SW3") (pin "P") (pinfunction "P_P") (pintype "passive"))
    )
    (net (code "70") (name "Net-(IC9A--IN)") (class "Default")
      (node (ref "IC9") (pin "2") (pinfunction "-IN_2") (pintype "input"))
      (node (ref "R48") (pin "1") (pinfunction "1_1") (pintype "passive"))
      (node (ref "R53") (pin "2") (pinfunction "2_2") (pintype "passive"))
    )
    (net (code "71") (name "Net-(IC9A-OUT)") (class "Default")
      (node (ref "IC9") (pin "1") (pinfunction "OUT_1") (pintype "output"))
      (node (ref "R43") (pin "1") (pinfunction "1_1") (pintype "passive"))
    )
    (net (code "72") (name "Net-(IC9B--IN)") (class "Default")
      (node (ref "IC9") (pin "6") (pinfunction "-IN_6") (pintype "input"))
      (node (ref "R54") (pin "1") (pinfunction "1_1") (pintype "passive"))
      (node (ref "R60") (pin "2") (pinfunction "2_2") (pintype "passive"))
    )
    (net (code "73") (name "Net-(IC9B-OUT)") (class "Default")
      (node (ref "IC9") (pin "7") (pinfunction "OUT_7") (pintype "output"))
      (node (ref "R49") (pin "1") (pinfunction "1_1") (pintype "passive"))
    )
    (net (code "74") (name "Net-(IC10A--IN)") (class "Default")
      (node (ref "C23") (pin "1") (pinfunction "1_1") (pintype "passive"))
      (node (ref "IC10") (pin "2") (pinfunction "-IN_2") (pintype "input"))
      (node (ref "R44") (pin "1") (pinfunction "1_1") (pintype "passive"))
      (node (ref "R50") (pin "2") (pinfunction "2_2") (pintype "passive"))
      (node (ref "R55") (pin "2") (pinfunction "2_2") (pintype "passive"))
      (node (ref "R61") (pin "2") (pinfunction "2_2") (pintype "passive"))
    )
    (net (code "75") (name "Net-(IC10B--IN)") (class "Default")
      (node (ref "C26") (pin "1") (pinfunction "1_1") (pintype "passive"))
      (node (ref "IC10") (pin "6") (pinfunction "-IN_6") (pintype "input"))
      (node (ref "R47") (pin "1") (pinfunction "1_1") (pintype "passive"))
      (node (ref "R51") (pin "2") (pinfunction "2_2") (pintype "passive"))
      (node (ref "R59") (pin "2") (pinfunction "2_2") (pintype "passive"))
      (node (ref "R63") (pin "2") (pinfunction "2_2") (pintype "passive"))
    )
    (net (code "76") (name "Net-(IC12A--IN)") (class "Default")
      (node (ref "C29") (pin "1") (pinfunction "1_1") (pintype "passive"))
      (node (ref "IC12") (pin "2") (pinfunction "-IN_2") (pintype "input"))
      (node (ref "R52") (pin "1") (pinfunction "1_1") (pintype "passive"))
      (node (ref "R64") (pin "2") (pinfunction "2_2") (pintype "passive"))
      (node (ref "R66") (pin "2") (pinfunction "2_2") (pintype "passive"))
    )
    (net (code "77") (name "Net-(IC12B--IN)") (class "Default")
      (node (ref "C31") (pin "1") (pinfunction "1_1") (pintype "passive"))
      (node (ref "IC12") (pin "6") (pinfunction "-IN_6") (pintype "input"))
      (node (ref "R58") (pin "1") (pinfunction "1_1") (pintype "passive"))
      (node (ref "R65") (pin "2") (pinfunction "2_2") (pintype "passive"))
      (node (ref "R67") (pin "2") (pinfunction "2_2") (pintype "passive"))
    )
    (net (code "78") (name "Net-(IC14-VIN)") (class "Default")
      (node (ref "C38") (pin "+") (pinfunction "+_+") (pintype "passive"))
      (node (ref "D1") (pin "C") (pinfunction "C_C") (pintype "passive"))
      (node (ref "IC14") (pin "3") (pinfunction "VIN_3") (pintype "input"))
    )
    (net (code "79") (name "Net-(IC16-AVCC)") (class "Default")
      (node (ref "C43") (pin "1") (pinfunction "1_1") (pintype "passive"))
      (node (ref "IC16") (pin "39") (pinfunction "AVCC_39") (pintype "bidirectional"))
      (node (ref "L1") (pin "2") (pinfunction "2_2") (pintype "passive"))
    )
    (net (code "80") (name "Net-(IC16-PA4)") (class "Default")
      (node (ref "IC16") (pin "44") (pinfunction "PA4_44") (pintype "bidirectional"))
      (node (ref "R74") (pin "1") (pinfunction "1_1") (pintype "passive"))
    )
    (net (code "81") (name "Net-(IC16-PA5)") (class "Default")
      (node (ref "IC16") (pin "1") (pinfunction "PA5_1") (pintype "bidirectional"))
      (node (ref "R73") (pin "1") (pinfunction "1_1") (pintype "passive"))
    )
    (net (code "82") (name "Net-(IC16-PA6)") (class "Default")
      (node (ref "IC16") (pin "2") (pinfunction "PA6_2") (pintype "bidirectional"))
      (node (ref "R72") (pin "1") (pinfunction "1_1") (pintype "passive"))
    )
    (net (code "83") (name "Net-(IC16-PA7)") (class "Default")
      (node (ref "IC16") (pin "3") (pinfunction "PA7_3") (pintype "bidirectional"))
      (node (ref "R71") (pin "1") (pinfunction "1_1") (pintype "passive"))
    )
    (net (code "84") (name "Net-(IC16-PC0)") (class "Default")
      (node (ref "IC16") (pin "10") (pinfunction "PC0_10") (pintype "bidirectional"))
      (node (ref "IC8") (pin "1") (pinfunction "I0_1") (pintype "input"))
    )
    (net (code "85") (name "Net-(IC16-PC4)") (class "Default")
      (node (ref "IC16") (pin "14") (pinfunction "PC4_14") (pintype "bidirectional"))
      (node (ref "IC6") (pin "1") (pinfunction "I0_1") (pintype "input"))
    )
    (net (code "86") (name "Net-(IC16-PD0)") (class "Default")
      (node (ref "IC16") (pin "20") (pinfunction "PD0_20") (pintype "bidirectional"))
      (node (ref "IC5") (pin "2") (pinfunction "I_2") (pintype "input"))
      (node (ref "SW2") (pin "S") (pinfunction "S_S") (pintype "passive"))
      (node (ref "SW3") (pin "S") (pinfunction "S_S") (pintype "passive"))
    )
    (net (code "87") (name "Net-(IC16-PE0)") (class "Default")
      (node (ref "IC16") (pin "28") (pinfunction "PE0_28") (pintype "bidirectional"))
      (node (ref "SW1") (pin "P") (pinfunction "P_P") (pintype "passive"))
    )
    (net (code "88") (name "Net-(IC16-PR0)") (class "Default")
      (node (ref "C42") (pin "2") (pinfunction "2_2") (pintype "passive"))
      (node (ref "IC16") (pin "36") (pinfunction "PR0_36") (pintype "bidirectional"))
      (node (ref "Q5") (pin "2") (pinfunction "2_2") (pintype "passive"))
    )
    (net (code "89") (name "Net-(IC16-PR1)") (class "Default")
      (node (ref "C44") (pin "2") (pinfunction "2_2") (pintype "passive"))
      (node (ref "IC16") (pin "37") (pinfunction "PR1_37") (pintype "bidirectional"))
      (node (ref "Q5") (pin "1") (pinfunction "1_1") (pintype "passive"))
    )
    (net (code "90") (name "Net-(J1-2)") (class "Default")
      (node (ref "J1") (pin "P2") (pinfunction "2_P2") (pintype "passive"))
      (node (ref "R20") (pin "2") (pinfunction "2_2") (pintype "passive"))
    )
    (net (code "91") (name "Net-(J1-3)") (class "Default")
      (node (ref "J1") (pin "P3") (pinfunction "3_P3") (pintype "passive"))
      (node (ref "J5") (pin "P2") (pinfunction "2_P2") (pintype "passive"))
      (node (ref "R21") (pin "2") (pinfunction "2_2") (pintype "passive"))
    )
    (net (code "92") (name "Net-(J2-2)") (class "Default")
      (node (ref "C1") (pin "1") (pinfunction "1_1") (pintype "passive"))
      (node (ref "J2") (pin "P2") (pinfunction "2_P2") (pintype "passive"))
      (node (ref "R1") (pin "2") (pinfunction "2_2") (pintype "passive"))
      (node (ref "R2") (pin "1") (pinfunction "1_1") (pintype "passive"))
    )
    (net (code "93") (name "Net-(J4-2)") (class "Default")
      (node (ref "J4") (pin "P2") (pinfunction "2_P2") (pintype "passive"))
      (node (ref "R5") (pin "P$1") (pinfunction "E_P$1") (pintype "passive"))
    )
    (net (code "94") (name "Net-(J5-3)") (class "Default")
      (node (ref "J5") (pin "P3") (pinfunction "3_P3") (pintype "passive"))
      (node (ref "J9") (pin "P2") (pinfunction "2_P2") (pintype "passive"))
      (node (ref "R22") (pin "2") (pinfunction "2_2") (pintype "passive"))
    )
    (net (code "95") (name "Net-(J8-2)") (class "Default")
      (node (ref "J8") (pin "P2") (pinfunction "2_P2") (pintype "passive"))
      (node (ref "R32") (pin "P$1") (pinfunction "E_P$1") (pintype "passive"))
    )
    (net (code "96") (name "Net-(J12-2)") (class "Default")
      (node (ref "J12") (pin "P2") (pinfunction "2_P2") (pintype "passive"))
      (node (ref "R42") (pin "P$1") (pinfunction "E_P$1") (pintype "passive"))
    )
    (net (code "97") (name "Net-(J13-2)") (class "Default")
      (node (ref "J13") (pin "P2") (pinfunction "2_P2") (pintype "passive"))
      (node (ref "J9") (pin "P3") (pinfunction "3_P3") (pintype "passive"))
      (node (ref "R56") (pin "2") (pinfunction "2_2") (pintype "passive"))
    )
    (net (code "98") (name "Net-(J13-3)") (class "Default")
      (node (ref "J13") (pin "P3") (pinfunction "3_P3") (pintype "passive"))
      (node (ref "R57") (pin "2") (pinfunction "2_2") (pintype "passive"))
    )
    (net (code "99") (name "Net-(J16-2)") (class "Default")
      (node (ref "J16") (pin "P2") (pinfunction "2_P2") (pintype "passive"))
      (node (ref "R69") (pin "P$1") (pinfunction "E_P$1") (pintype "passive"))
    )
    (net (code "100") (name "Net-(J17-3)") (class "Default")
      (node (ref "J17") (pin "P3") (pinfunction "3_P3") (pintype "passive"))
      (node (ref "R33") (pin "2") (pinfunction "2_2") (pintype "passive"))
      (node (ref "R34") (pin "2") (pinfunction "2_2") (pintype "passive"))
    )
    (net (code "101") (name "Net-(LED1-PadA)") (class "Default")
      (node (ref "LED1") (pin "A") (pinfunction "A_A") (pintype "passive"))
      (node (ref "R71") (pin "2") (pinfunction "2_2") (pintype "passive"))
    )
    (net (code "102") (name "Net-(LED2-PadA)") (class "Default")
      (node (ref "LED2") (pin "A") (pinfunction "A_A") (pintype "passive"))
      (node (ref "R72") (pin "2") (pinfunction "2_2") (pintype "passive"))
    )
    (net (code "103") (name "Net-(LED3-PadA)") (class "Default")
      (node (ref "LED3") (pin "A") (pinfunction "A_A") (pintype "passive"))
      (node (ref "R73") (pin "2") (pinfunction "2_2") (pintype "passive"))
    )
    (net (code "104") (name "Net-(LED4-PadA)") (class "Default")
      (node (ref "LED4") (pin "A") (pinfunction "A_A") (pintype "passive"))
      (node (ref "R74") (pin "2") (pinfunction "2_2") (pintype "passive"))
    )
    (net (code "105") (name "Net-(Q1-PadB)") (class "Default")
      (node (ref "Q1") (pin "B") (pinfunction "B_B") (pintype "passive"))
      (node (ref "R21") (pin "1") (pinfunction "1_1") (pintype "passive"))
    )
    (net (code "106") (name "Net-(Q2-PadB)") (class "Default")
      (node (ref "Q2") (pin "B") (pinfunction "B_B") (pintype "passive"))
      (node (ref "R22") (pin "1") (pinfunction "1_1") (pintype "passive"))
    )
    (net (code "107") (name "Net-(Q3-PadB)") (class "Default")
      (node (ref "Q3") (pin "B") (pinfunction "B_B") (pintype "passive"))
      (node (ref "R56") (pin "1") (pinfunction "1_1") (pintype "passive"))
    )
    (net (code "108") (name "Net-(Q4-PadB)") (class "Default")
      (node (ref "Q4") (pin "B") (pinfunction "B_B") (pintype "passive"))
      (node (ref "R57") (pin "1") (pinfunction "1_1") (pintype "passive"))
    )
    (net (code "109") (name "PDICLK") (class "Default")
      (node (ref "IC16") (pin "35") (pinfunction "RESET_35") (pintype "bidirectional"))
      (node (ref "J20") (pin "5") (pinfunction "5_5") (pintype "passive"))
      (node (ref "R70") (pin "1") (pinfunction "1_1") (pintype "passive"))
    )
    (net (code "110") (name "PDIDATA") (class "Default")
      (node (ref "IC16") (pin "34") (pinfunction "PDI_DATA_34") (pintype "bidirectional"))
      (node (ref "J20") (pin "1") (pinfunction "1_1") (pintype "passive"))
    )
    (net (code "111") (name "SW1") (class "Default")
      (node (ref "IC16") (pin "4") (pinfunction "PB0_4") (pintype "bidirectional"))
      (node (ref "SW7") (pin "1") (pinfunction "1_1") (pintype "passive"))
      (node (ref "SW7") (pin "2") (pinfunction "2_2") (pintype "passive"))
    )
    (net (code "112") (name "SW2") (class "Default")
      (node (ref "IC16") (pin "5") (pinfunction "PB1_5") (pintype "bidirectional"))
      (node (ref "SW6") (pin "1") (pinfunction "1_1") (pintype "passive"))
      (node (ref "SW6") (pin "2") (pinfunction "2_2") (pintype "passive"))
    )
    (net (code "113") (name "SW3") (class "Default")
      (node (ref "IC16") (pin "6") (pinfunction "PB2_6") (pintype "bidirectional"))
      (node (ref "SW5") (pin "1") (pinfunction "1_1") (pintype "passive"))
      (node (ref "SW5") (pin "2") (pinfunction "2_2") (pintype "passive"))
    )
    (net (code "114") (name "SW4") (class "Default")
      (node (ref "IC16") (pin "7") (pinfunction "PB3_7") (pintype "bidirectional"))
      (node (ref "SW4") (pin "1") (pinfunction "1_1") (pintype "passive"))
      (node (ref "SW4") (pin "2") (pinfunction "2_2") (pintype "passive"))
    )
    (net (code "115") (name "SW_MIDI_LEARN") (class "Default")
      (node (ref "IC16") (pin "11") (pinfunction "PC1_11") (pintype "bidirectional"))
      (node (ref "J18") (pin "2") (pinfunction "2_2") (pintype "passive"))
    )
    (net (code "116") (name "SW_MIDI_MODE") (class "Default")
      (node (ref "IC16") (pin "13") (pinfunction "PC3_13") (pintype "bidirectional"))
      (node (ref "J18") (pin "6") (pinfunction "6_6") (pintype "passive"))
    )
    (net (code "117") (name "VCC") (class "Default")
      (node (ref "C15") (pin "1") (pinfunction "1_1") (pintype "passive"))
      (node (ref "C18") (pin "+") (pinfunction "+_+") (pintype "passive"))
      (node (ref "C22") (pin "1") (pinfunction "1_1") (pintype "passive"))
      (node (ref "C3") (pin "1") (pinfunction "1_1") (pintype "passive"))
      (node (ref "D1") (pin "A") (pinfunction "A_A") (pintype "passive"))
      (node (ref "D2") (pin "C") (pinfunction "C_C") (pintype "passive"))
      (node (ref "IC2") (pin "8") (pinfunction "V+_8") (pintype "power_in"))
      (node (ref "IC7") (pin "8") (pinfunction "V+_8") (pintype "power_in"))
      (node (ref "IC9") (pin "8") (pinfunction "V+_8") (pintype "power_in"))
      (node (ref "R2") (pin "2") (pinfunction "2_2") (pintype "passive"))
    )
    (net (code "118") (name "VEE") (class "Default")
      (node (ref "C11") (pin "2") (pinfunction "2_2") (pintype "passive"))
      (node (ref "C19") (pin "-") (pinfunction "-_-") (pintype "passive"))
      (node (ref "C20") (pin "2") (pinfunction "2_2") (pintype "passive"))
      (node (ref "C30") (pin "2") (pinfunction "2_2") (pintype "passive"))
      (node (ref "D3") (pin "A") (pinfunction "A_A") (pintype "passive"))
      (node (ref "IC2") (pin "4") (pinfunction "V-_4") (pintype "power_in"))
      (node (ref "IC7") (pin "4") (pinfunction "V-_4") (pintype "power_in"))
      (node (ref "IC9") (pin "4") (pinfunction "V-_4") (pintype "power_in"))
      (node (ref "R3") (pin "1") (pinfunction "1_1") (pintype "passive"))
    )
    (net (code "119") (name "unconnected-(IC15-OUTB-Pad6)") (class "Default")
      (node (ref "IC15") (pin "6") (pinfunction "OUTB_6") (pintype "output"))
    )
    (net (code "120") (name "unconnected-(IC16-PD1-Pad21)") (class "Default")
      (node (ref "IC16") (pin "21") (pinfunction "PD1_21") (pintype "bidirectional"))
    )
    (net (code "121") (name "unconnected-(IC16-PD2-Pad22)") (class "Default")
      (node (ref "IC16") (pin "22") (pinfunction "PD2_22") (pintype "bidirectional"))
    )
    (net (code "122") (name "unconnected-(IC16-PE1-Pad29)") (class "Default")
      (node (ref "IC16") (pin "29") (pinfunction "PE1_29") (pintype "bidirectional"))
    )
    (net (code "123") (name "unconnected-(IC16-PE2-Pad32)") (class "Default")
      (node (ref "IC16") (pin "32") (pinfunction "PE2_32") (pintype "bidirectional"))
    )
    (net (code "124") (name "unconnected-(IC16-PE3-Pad33)") (class "Default")
      (node (ref "IC16") (pin "33") (pinfunction "PE3_33") (pintype "bidirectional"))
    )
    (net (code "125") (name "unconnected-(J3-2-PadP2)") (class "Default")
      (node (ref "J3") (pin "P2") (pinfunction "2_P2") (pintype "passive"))
    )
    (net (code "126") (name "unconnected-(J7-2-PadP2)") (class "Default")
      (node (ref "J7") (pin "P2") (pinfunction "2_P2") (pintype "passive"))
    )
    (net (code "127") (name "unconnected-(J11-2-PadP2)") (class "Default")
      (node (ref "J11") (pin "P2") (pinfunction "2_P2") (pintype "passive"))
    )
    (net (code "128") (name "unconnected-(J15-2-PadP2)") (class "Default")
      (node (ref "J15") (pin "P2") (pinfunction "2_P2") (pintype "passive"))
    )
    (net (code "129") (name "unconnected-(J17-2-PadP2)") (class "Default")
      (node (ref "J17") (pin "P2") (pinfunction "2_P2") (pintype "passive"))
    )
    (net (code "130") (name "unconnected-(J20-Pad3)") (class "Default")
      (node (ref "J20") (pin "3") (pinfunction "3_3") (pintype "passive"))
    )
    (net (code "131") (name "unconnected-(J20-Pad4)") (class "Default")
      (node (ref "J20") (pin "4") (pinfunction "4_4") (pintype "passive"))
    )
  )
)
